# microzed_breakout_v0_6.net
KiCad netlist of a schematic drawn in EAGLE
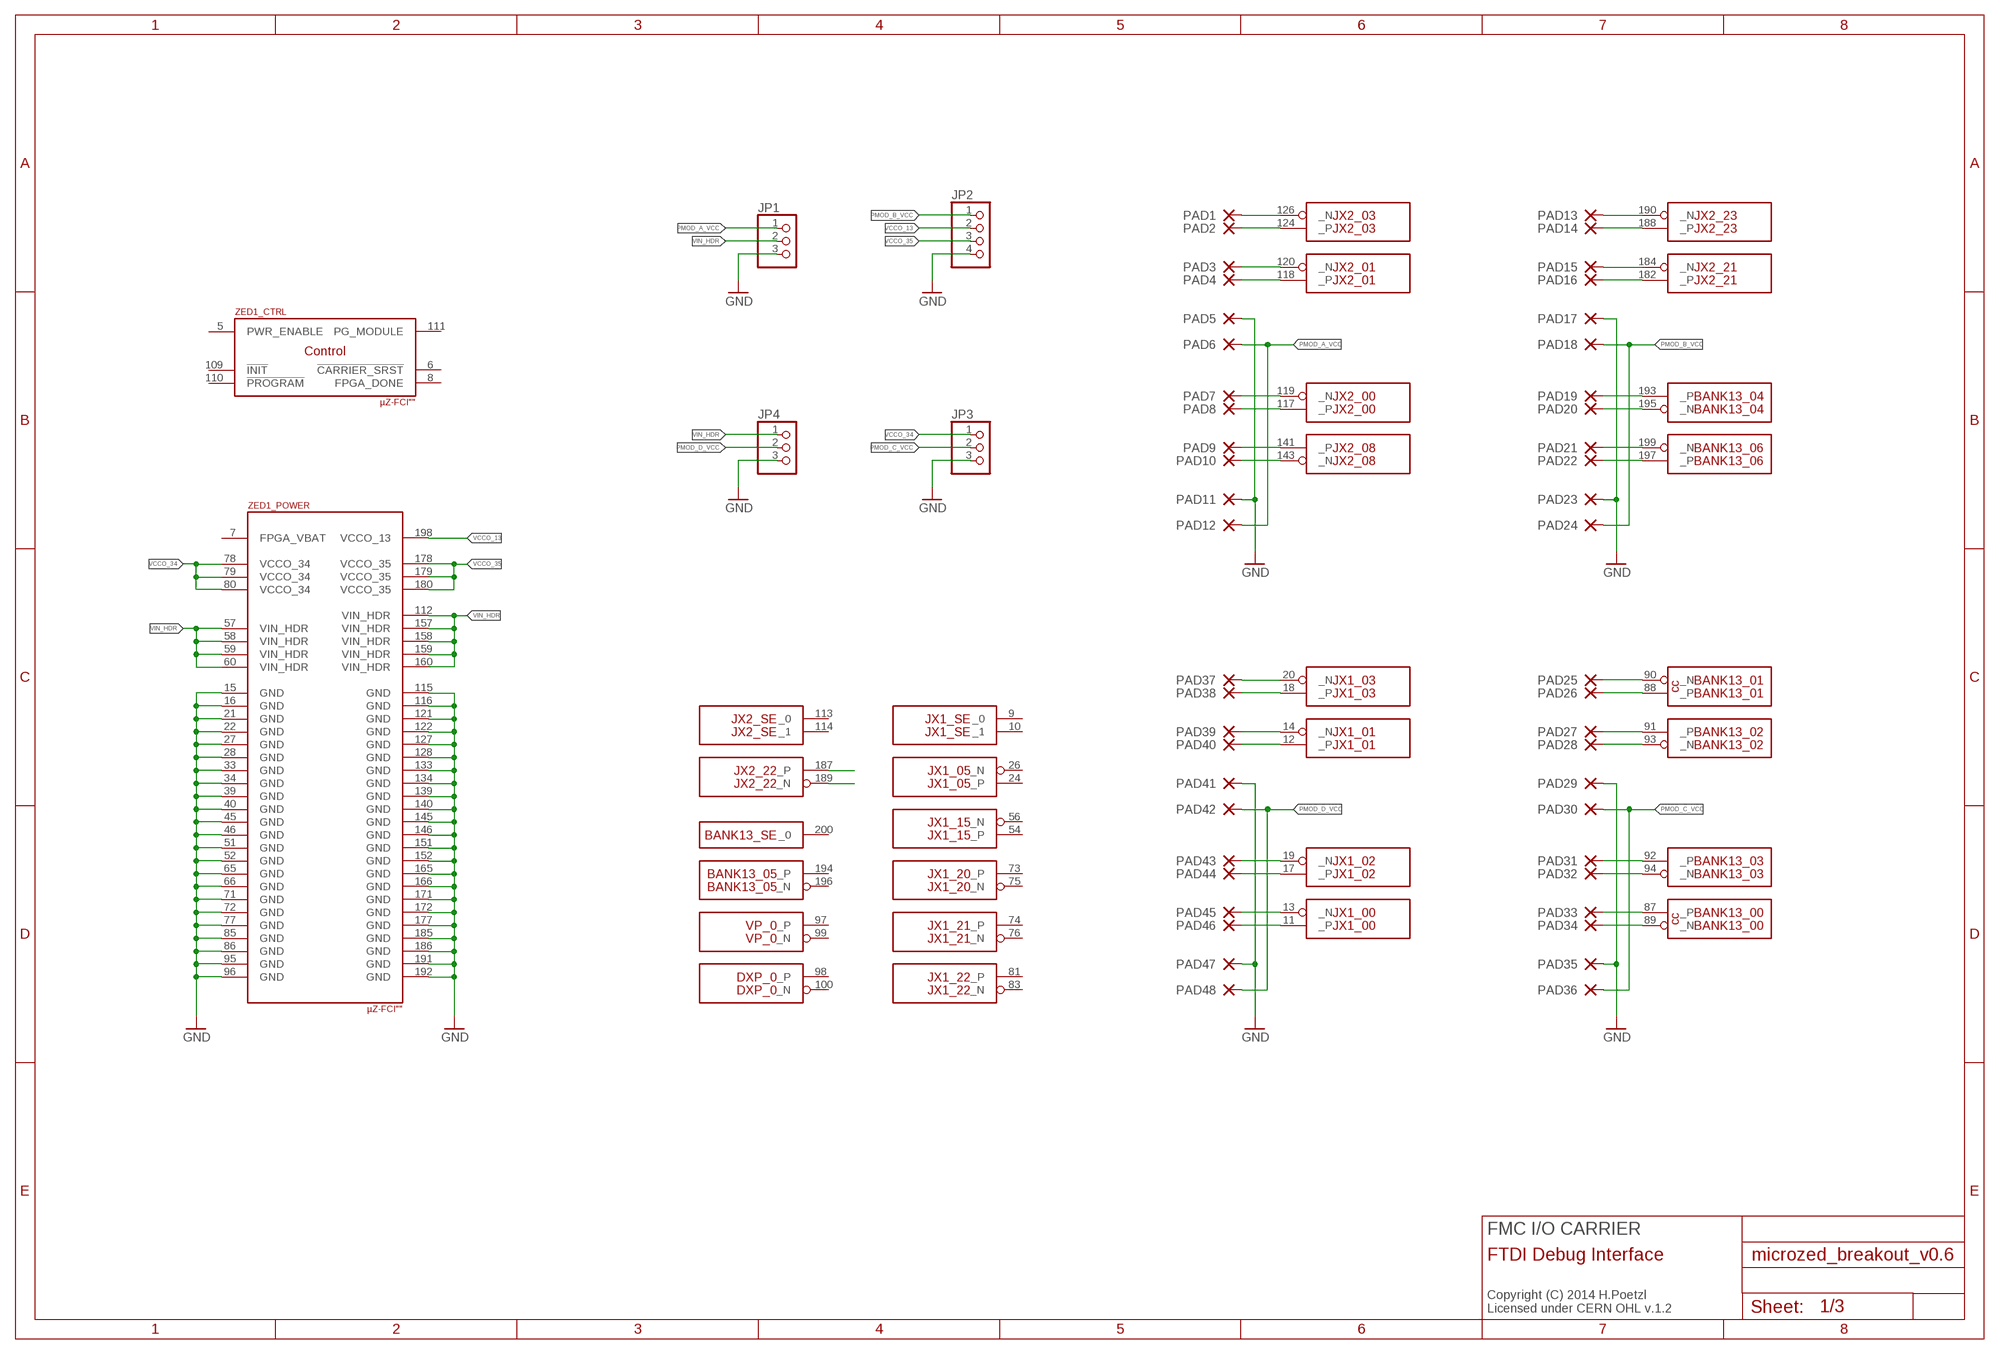
[diagram p0: schematic, sheet 1]
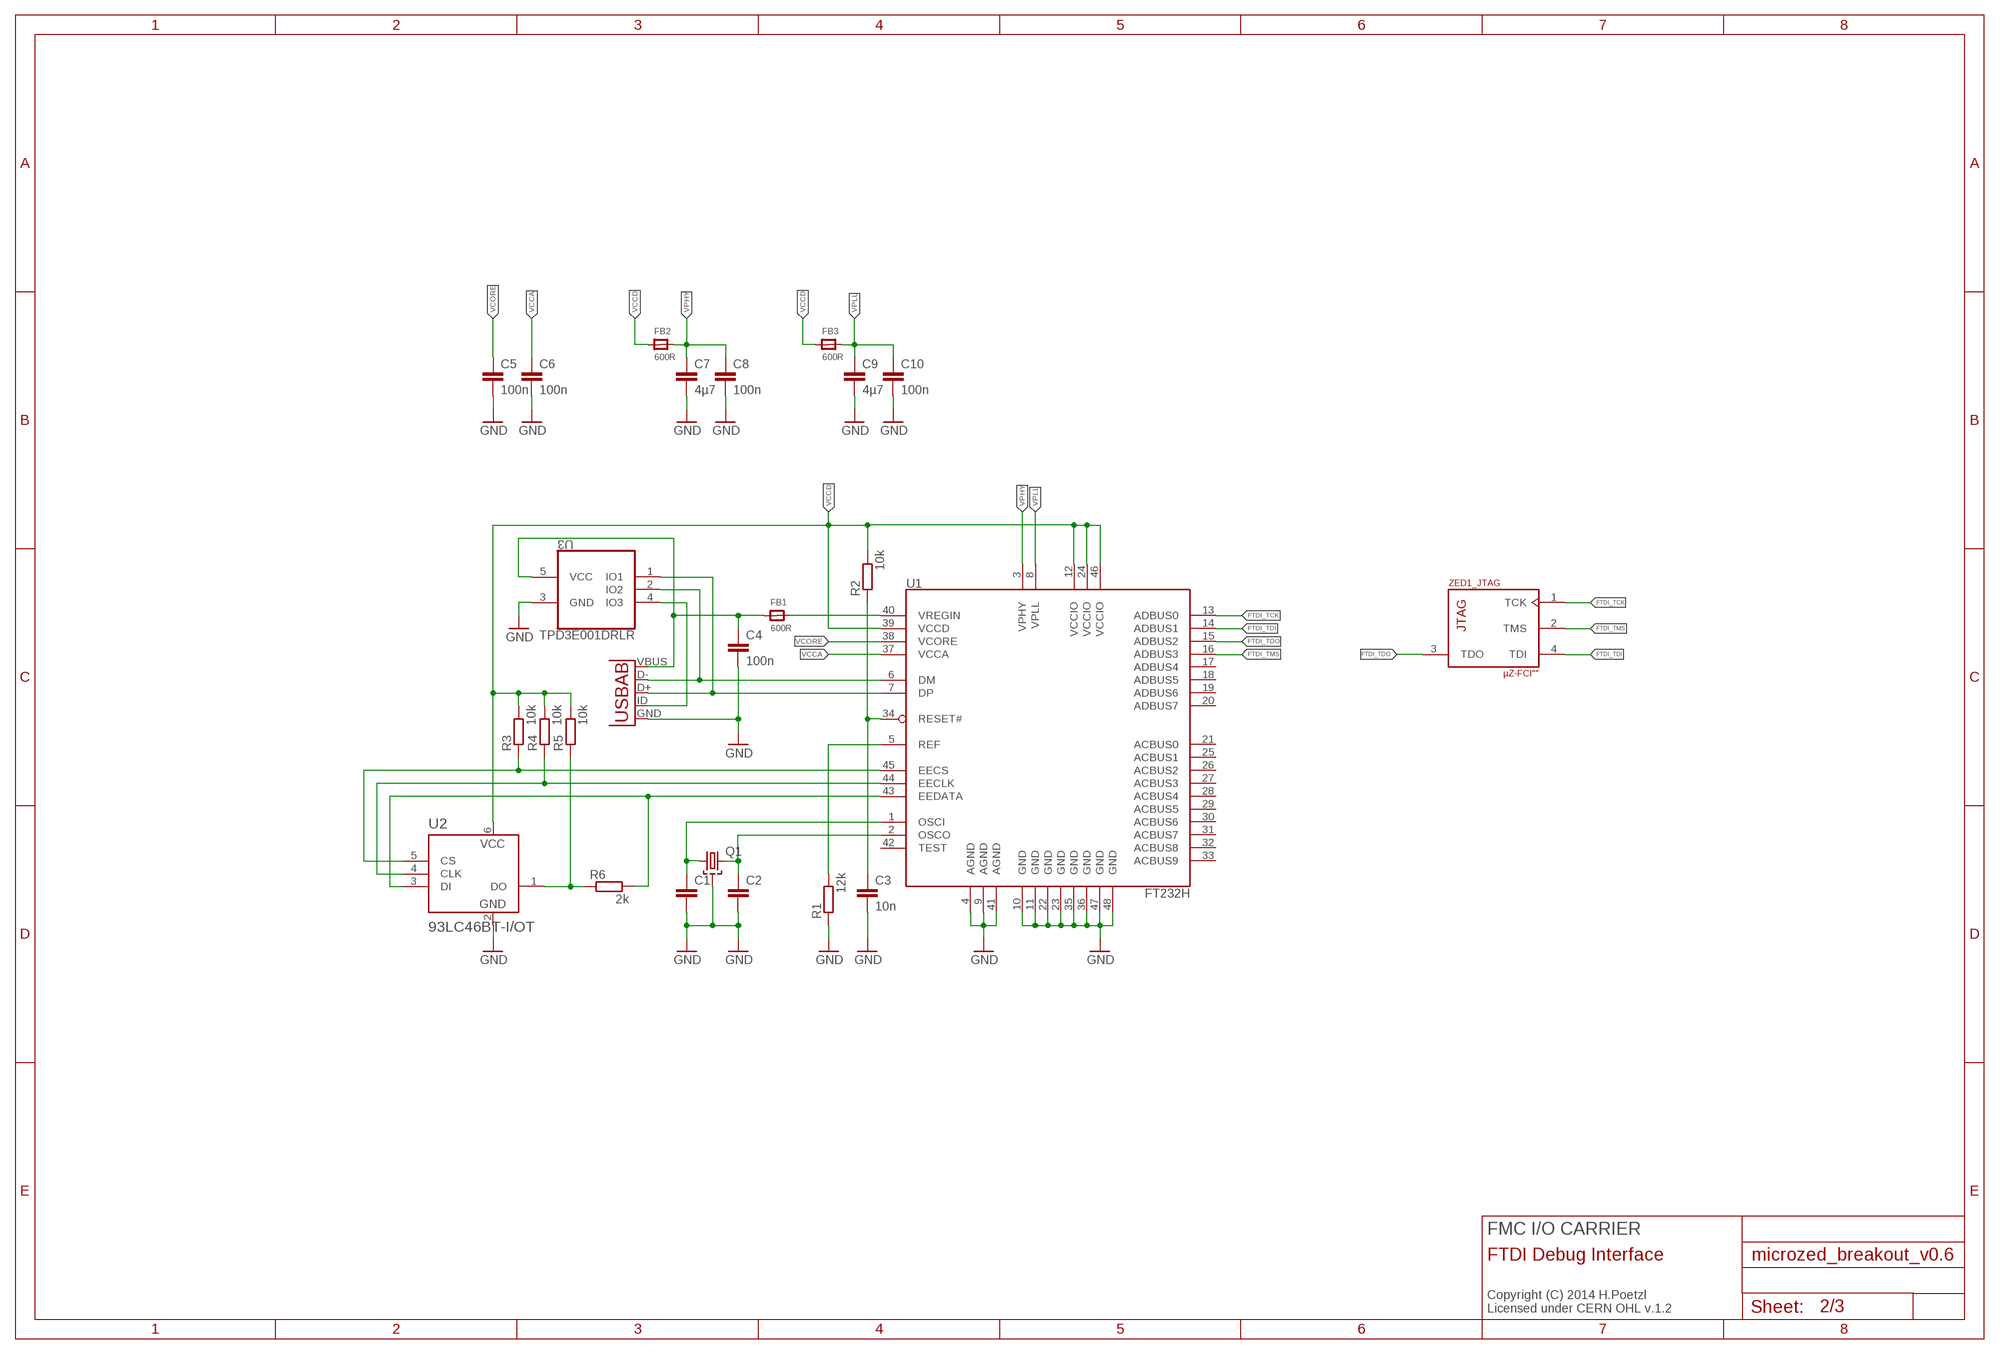
[diagram p1: schematic, sheet 2]
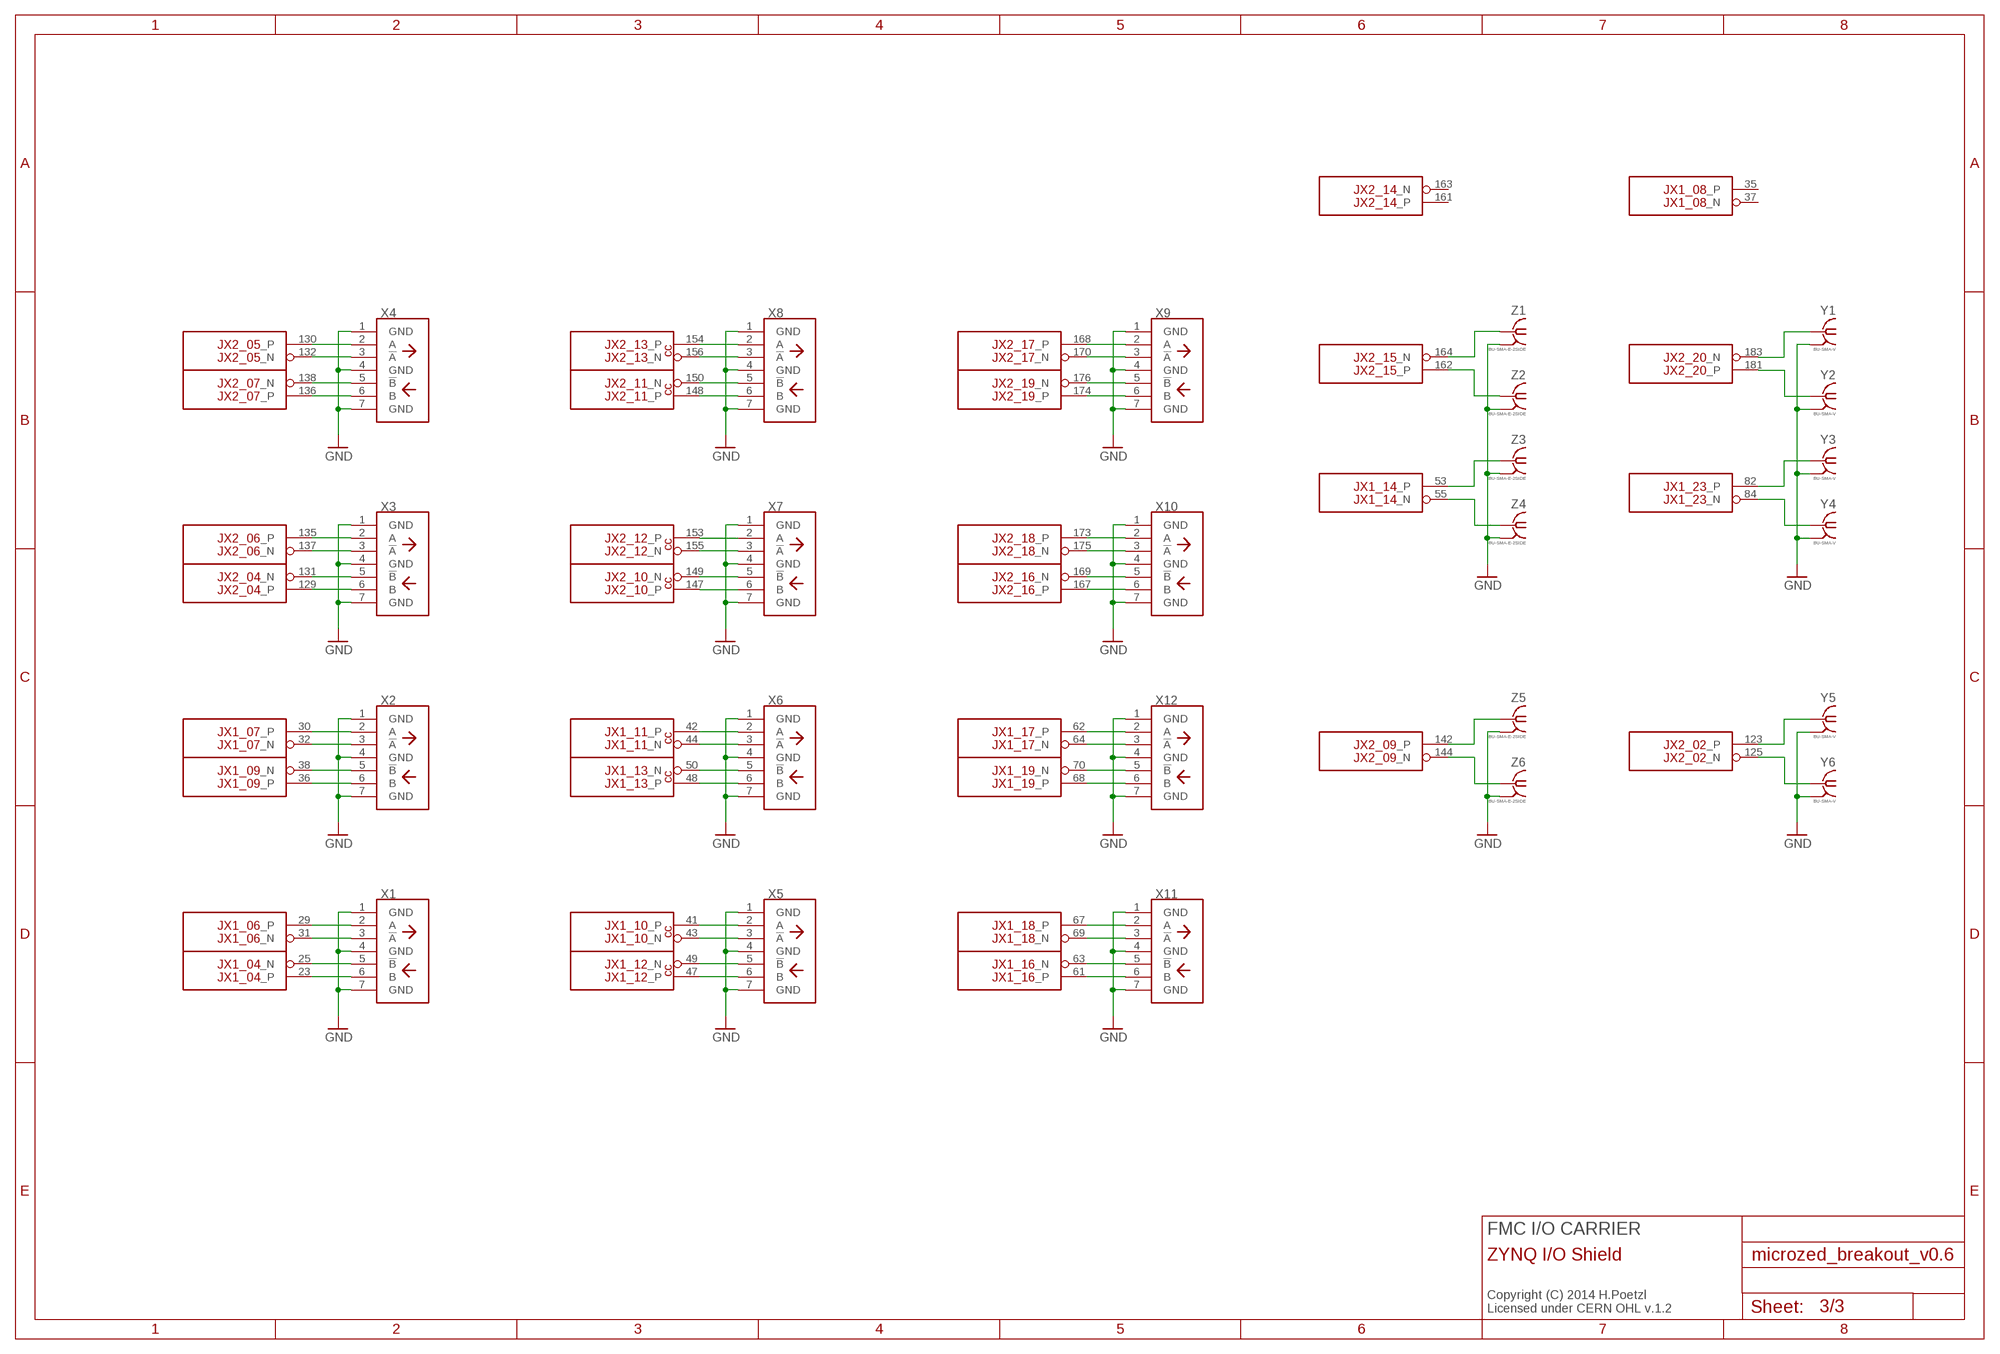
[diagram p2: schematic, sheet 3]

(export (version "E")
  (design (tool "Eeschema 10.0.6"))
  (components
    (comp (ref "JP1")
      (value "PINHD-1X03_2.54")
      (footprint "eagle-import:1X03")
      (libsource (lib "eagle-import") (part "PINHD-1X03_2.54"))
    )
    (comp (ref "JP2")
      (value "PINHD-1X04_2.54")
      (footprint "eagle-import:1X04")
      (libsource (lib "eagle-import") (part "PINHD-1X04_2.54"))
    )
    (comp (ref "JP3")
      (value "PINHD-1X03_2.54")
      (footprint "eagle-import:1X03")
      (libsource (lib "eagle-import") (part "PINHD-1X03_2.54"))
    )
    (comp (ref "JP4")
      (value "PINHD-1X03_2.54")
      (footprint "eagle-import:1X03")
      (libsource (lib "eagle-import") (part "PINHD-1X03_2.54"))
    )
    (comp (ref "PAD1")
      (value "SMD-PAD1.6X3.8MM-U")
      (footprint "eagle-import:1.6X3.8U-MM")
      (libsource (lib "eagle-import") (part "SMD-PAD1.6X3.8MM-U"))
    )
    (comp (ref "PAD2")
      (value "SMD-PAD1.6X3.8MM-U")
      (footprint "eagle-import:1.6X3.8U-MM")
      (libsource (lib "eagle-import") (part "SMD-PAD1.6X3.8MM-U"))
    )
    (comp (ref "PAD3")
      (value "SMD-PAD1.6X3.8MM-U")
      (footprint "eagle-import:1.6X3.8U-MM")
      (libsource (lib "eagle-import") (part "SMD-PAD1.6X3.8MM-U"))
    )
    (comp (ref "PAD4")
      (value "SMD-PAD1.6X3.8MM-U")
      (footprint "eagle-import:1.6X3.8U-MM")
      (libsource (lib "eagle-import") (part "SMD-PAD1.6X3.8MM-U"))
    )
    (comp (ref "PAD5")
      (value "SMD-PAD1.6X3.8MM-U")
      (footprint "eagle-import:1.6X3.8U-MM")
      (libsource (lib "eagle-import") (part "SMD-PAD1.6X3.8MM-U"))
    )
    (comp (ref "PAD6")
      (value "SMD-PAD1.6X3.8MM-U")
      (footprint "eagle-import:1.6X3.8U-MM")
      (libsource (lib "eagle-import") (part "SMD-PAD1.6X3.8MM-U"))
    )
    (comp (ref "PAD7")
      (value "SMD-PAD1.6X3.8MM-U")
      (footprint "eagle-import:1.6X3.8U-MM")
      (libsource (lib "eagle-import") (part "SMD-PAD1.6X3.8MM-U"))
    )
    (comp (ref "PAD8")
      (value "SMD-PAD1.6X3.8MM-U")
      (footprint "eagle-import:1.6X3.8U-MM")
      (libsource (lib "eagle-import") (part "SMD-PAD1.6X3.8MM-U"))
    )
    (comp (ref "PAD9")
      (value "SMD-PAD1.6X3.8MM-U")
      (footprint "eagle-import:1.6X3.8U-MM")
      (libsource (lib "eagle-import") (part "SMD-PAD1.6X3.8MM-U"))
    )
    (comp (ref "PAD10")
      (value "SMD-PAD1.6X3.8MM-U")
      (footprint "eagle-import:1.6X3.8U-MM")
      (libsource (lib "eagle-import") (part "SMD-PAD1.6X3.8MM-U"))
    )
    (comp (ref "PAD11")
      (value "SMD-PAD1.6X3.8MM-U")
      (footprint "eagle-import:1.6X3.8U-MM")
      (libsource (lib "eagle-import") (part "SMD-PAD1.6X3.8MM-U"))
    )
    (comp (ref "PAD12")
      (value "SMD-PAD1.6X3.8MM-U")
      (footprint "eagle-import:1.6X3.8U-MM")
      (libsource (lib "eagle-import") (part "SMD-PAD1.6X3.8MM-U"))
    )
    (comp (ref "PAD13")
      (value "SMD-PAD1.6X3.8MM-U")
      (footprint "eagle-import:1.6X3.8U-MM")
      (libsource (lib "eagle-import") (part "SMD-PAD1.6X3.8MM-U"))
    )
    (comp (ref "PAD14")
      (value "SMD-PAD1.6X3.8MM-U")
      (footprint "eagle-import:1.6X3.8U-MM")
      (libsource (lib "eagle-import") (part "SMD-PAD1.6X3.8MM-U"))
    )
    (comp (ref "PAD15")
      (value "SMD-PAD1.6X3.8MM-U")
      (footprint "eagle-import:1.6X3.8U-MM")
      (libsource (lib "eagle-import") (part "SMD-PAD1.6X3.8MM-U"))
    )
    (comp (ref "PAD16")
      (value "SMD-PAD1.6X3.8MM-U")
      (footprint "eagle-import:1.6X3.8U-MM")
      (libsource (lib "eagle-import") (part "SMD-PAD1.6X3.8MM-U"))
    )
    (comp (ref "PAD17")
      (value "SMD-PAD1.6X3.8MM-U")
      (footprint "eagle-import:1.6X3.8U-MM")
      (libsource (lib "eagle-import") (part "SMD-PAD1.6X3.8MM-U"))
    )
    (comp (ref "PAD18")
      (value "SMD-PAD1.6X3.8MM-U")
      (footprint "eagle-import:1.6X3.8U-MM")
      (libsource (lib "eagle-import") (part "SMD-PAD1.6X3.8MM-U"))
    )
    (comp (ref "PAD19")
      (value "SMD-PAD1.6X3.8MM-U")
      (footprint "eagle-import:1.6X3.8U-MM")
      (libsource (lib "eagle-import") (part "SMD-PAD1.6X3.8MM-U"))
    )
    (comp (ref "PAD20")
      (value "SMD-PAD1.6X3.8MM-U")
      (footprint "eagle-import:1.6X3.8U-MM")
      (libsource (lib "eagle-import") (part "SMD-PAD1.6X3.8MM-U"))
    )
    (comp (ref "PAD21")
      (value "SMD-PAD1.6X3.8MM-U")
      (footprint "eagle-import:1.6X3.8U-MM")
      (libsource (lib "eagle-import") (part "SMD-PAD1.6X3.8MM-U"))
    )
    (comp (ref "PAD22")
      (value "SMD-PAD1.6X3.8MM-U")
      (footprint "eagle-import:1.6X3.8U-MM")
      (libsource (lib "eagle-import") (part "SMD-PAD1.6X3.8MM-U"))
    )
    (comp (ref "PAD23")
      (value "SMD-PAD1.6X3.8MM-U")
      (footprint "eagle-import:1.6X3.8U-MM")
      (libsource (lib "eagle-import") (part "SMD-PAD1.6X3.8MM-U"))
    )
    (comp (ref "PAD24")
      (value "SMD-PAD1.6X3.8MM-U")
      (footprint "eagle-import:1.6X3.8U-MM")
      (libsource (lib "eagle-import") (part "SMD-PAD1.6X3.8MM-U"))
    )
    (comp (ref "PAD25")
      (value "SMD-PAD1.6X3.8MM-U")
      (footprint "eagle-import:1.6X3.8U-MM")
      (libsource (lib "eagle-import") (part "SMD-PAD1.6X3.8MM-U"))
    )
    (comp (ref "PAD26")
      (value "SMD-PAD1.6X3.8MM-U")
      (footprint "eagle-import:1.6X3.8U-MM")
      (libsource (lib "eagle-import") (part "SMD-PAD1.6X3.8MM-U"))
    )
    (comp (ref "PAD27")
      (value "SMD-PAD1.6X3.8MM-U")
      (footprint "eagle-import:1.6X3.8U-MM")
      (libsource (lib "eagle-import") (part "SMD-PAD1.6X3.8MM-U"))
    )
    (comp (ref "PAD28")
      (value "SMD-PAD1.6X3.8MM-U")
      (footprint "eagle-import:1.6X3.8U-MM")
      (libsource (lib "eagle-import") (part "SMD-PAD1.6X3.8MM-U"))
    )
    (comp (ref "PAD29")
      (value "SMD-PAD1.6X3.8MM-U")
      (footprint "eagle-import:1.6X3.8U-MM")
      (libsource (lib "eagle-import") (part "SMD-PAD1.6X3.8MM-U"))
    )
    (comp (ref "PAD30")
      (value "SMD-PAD1.6X3.8MM-U")
      (footprint "eagle-import:1.6X3.8U-MM")
      (libsource (lib "eagle-import") (part "SMD-PAD1.6X3.8MM-U"))
    )
    (comp (ref "PAD31")
      (value "SMD-PAD1.6X3.8MM-U")
      (footprint "eagle-import:1.6X3.8U-MM")
      (libsource (lib "eagle-import") (part "SMD-PAD1.6X3.8MM-U"))
    )
    (comp (ref "PAD32")
      (value "SMD-PAD1.6X3.8MM-U")
      (footprint "eagle-import:1.6X3.8U-MM")
      (libsource (lib "eagle-import") (part "SMD-PAD1.6X3.8MM-U"))
    )
    (comp (ref "PAD33")
      (value "SMD-PAD1.6X3.8MM-U")
      (footprint "eagle-import:1.6X3.8U-MM")
      (libsource (lib "eagle-import") (part "SMD-PAD1.6X3.8MM-U"))
    )
    (comp (ref "PAD34")
      (value "SMD-PAD1.6X3.8MM-U")
      (footprint "eagle-import:1.6X3.8U-MM")
      (libsource (lib "eagle-import") (part "SMD-PAD1.6X3.8MM-U"))
    )
    (comp (ref "PAD35")
      (value "SMD-PAD1.6X3.8MM-U")
      (footprint "eagle-import:1.6X3.8U-MM")
      (libsource (lib "eagle-import") (part "SMD-PAD1.6X3.8MM-U"))
    )
    (comp (ref "PAD36")
      (value "SMD-PAD1.6X3.8MM-U")
      (footprint "eagle-import:1.6X3.8U-MM")
      (libsource (lib "eagle-import") (part "SMD-PAD1.6X3.8MM-U"))
    )
    (comp (ref "PAD37")
      (value "SMD-PAD1.6X3.8MM-U")
      (footprint "eagle-import:1.6X3.8U-MM")
      (libsource (lib "eagle-import") (part "SMD-PAD1.6X3.8MM-U"))
    )
    (comp (ref "PAD38")
      (value "SMD-PAD1.6X3.8MM-U")
      (footprint "eagle-import:1.6X3.8U-MM")
      (libsource (lib "eagle-import") (part "SMD-PAD1.6X3.8MM-U"))
    )
    (comp (ref "PAD39")
      (value "SMD-PAD1.6X3.8MM-U")
      (footprint "eagle-import:1.6X3.8U-MM")
      (libsource (lib "eagle-import") (part "SMD-PAD1.6X3.8MM-U"))
    )
    (comp (ref "PAD40")
      (value "SMD-PAD1.6X3.8MM-U")
      (footprint "eagle-import:1.6X3.8U-MM")
      (libsource (lib "eagle-import") (part "SMD-PAD1.6X3.8MM-U"))
    )
    (comp (ref "PAD41")
      (value "SMD-PAD1.6X3.8MM-U")
      (footprint "eagle-import:1.6X3.8U-MM")
      (libsource (lib "eagle-import") (part "SMD-PAD1.6X3.8MM-U"))
    )
    (comp (ref "PAD42")
      (value "SMD-PAD1.6X3.8MM-U")
      (footprint "eagle-import:1.6X3.8U-MM")
      (libsource (lib "eagle-import") (part "SMD-PAD1.6X3.8MM-U"))
    )
    (comp (ref "PAD43")
      (value "SMD-PAD1.6X3.8MM-U")
      (footprint "eagle-import:1.6X3.8U-MM")
      (libsource (lib "eagle-import") (part "SMD-PAD1.6X3.8MM-U"))
    )
    (comp (ref "PAD44")
      (value "SMD-PAD1.6X3.8MM-U")
      (footprint "eagle-import:1.6X3.8U-MM")
      (libsource (lib "eagle-import") (part "SMD-PAD1.6X3.8MM-U"))
    )
    (comp (ref "PAD45")
      (value "SMD-PAD1.6X3.8MM-U")
      (footprint "eagle-import:1.6X3.8U-MM")
      (libsource (lib "eagle-import") (part "SMD-PAD1.6X3.8MM-U"))
    )
    (comp (ref "PAD46")
      (value "SMD-PAD1.6X3.8MM-U")
      (footprint "eagle-import:1.6X3.8U-MM")
      (libsource (lib "eagle-import") (part "SMD-PAD1.6X3.8MM-U"))
    )
    (comp (ref "PAD47")
      (value "SMD-PAD1.6X3.8MM-U")
      (footprint "eagle-import:1.6X3.8U-MM")
      (libsource (lib "eagle-import") (part "SMD-PAD1.6X3.8MM-U"))
    )
    (comp (ref "PAD48")
      (value "SMD-PAD1.6X3.8MM-U")
      (footprint "eagle-import:1.6X3.8U-MM")
      (libsource (lib "eagle-import") (part "SMD-PAD1.6X3.8MM-U"))
    )
    (comp (ref "ZED1")
      (value "µZ-FCI\"\"")
      (footprint "eagle-import:µZ")
      (libsource (lib "eagle-import") (part "µZ-FCI{dblquote}{dblquote}"))
    )
    (comp (ref "C1")
      (value "C-EUC0402K")
      (footprint "eagle-import:C0402K")
      (libsource (lib "eagle-import") (part "C-EUC0402K"))
    )
    (comp (ref "C2")
      (value "C-EUC0402K")
      (footprint "eagle-import:C0402K")
      (libsource (lib "eagle-import") (part "C-EUC0402K"))
    )
    (comp (ref "C3")
      (value "10n")
      (footprint "eagle-import:C0402K")
      (libsource (lib "eagle-import") (part "C-EUC0402K"))
    )
    (comp (ref "C4")
      (value "100n")
      (footprint "eagle-import:C0402K")
      (libsource (lib "eagle-import") (part "C-EUC0402K"))
    )
    (comp (ref "C5")
      (value "100n")
      (footprint "eagle-import:C0402K")
      (libsource (lib "eagle-import") (part "C-EUC0402K"))
    )
    (comp (ref "C6")
      (value "100n")
      (footprint "eagle-import:C0402K")
      (libsource (lib "eagle-import") (part "C-EUC0402K"))
    )
    (comp (ref "C7")
      (value "4µ7")
      (footprint "eagle-import:C0402K")
      (libsource (lib "eagle-import") (part "C-EUC0402K"))
    )
    (comp (ref "C8")
      (value "100n")
      (footprint "eagle-import:C0402K")
      (libsource (lib "eagle-import") (part "C-EUC0402K"))
    )
    (comp (ref "C9")
      (value "4µ7")
      (footprint "eagle-import:C0402K")
      (libsource (lib "eagle-import") (part "C-EUC0402K"))
    )
    (comp (ref "C10")
      (value "100n")
      (footprint "eagle-import:C0402K")
      (libsource (lib "eagle-import") (part "C-EUC0402K"))
    )
    (comp (ref "FB1")
      (value "600R")
      (footprint "eagle-import:_0603MP")
      (libsource (lib "eagle-import") (part "FERRITE_0603MP"))
    )
    (comp (ref "FB2")
      (value "600R")
      (footprint "eagle-import:_0603MP")
      (libsource (lib "eagle-import") (part "FERRITE_0603MP"))
    )
    (comp (ref "FB3")
      (value "600R")
      (footprint "eagle-import:_0603MP")
      (libsource (lib "eagle-import") (part "FERRITE_0603MP"))
    )
    (comp (ref "Q1")
      (value "SMD-4P-2G-3.2X2.5")
      (footprint "eagle-import:ABM8G")
      (libsource (lib "eagle-import") (part "SMD-4P-2G-3.2X2.5"))
    )
    (comp (ref "R1")
      (value "12k")
      (footprint "eagle-import:R0402")
      (libsource (lib "eagle-import") (part "R-EU_R0402"))
    )
    (comp (ref "R2")
      (value "10k")
      (footprint "eagle-import:R0402")
      (libsource (lib "eagle-import") (part "R-EU_R0402"))
    )
    (comp (ref "R3")
      (value "10k")
      (footprint "eagle-import:R0402")
      (libsource (lib "eagle-import") (part "R-EU_R0402"))
    )
    (comp (ref "R4")
      (value "10k")
      (footprint "eagle-import:R0402")
      (libsource (lib "eagle-import") (part "R-EU_R0402"))
    )
    (comp (ref "R5")
      (value "10k")
      (footprint "eagle-import:R0402")
      (libsource (lib "eagle-import") (part "R-EU_R0402"))
    )
    (comp (ref "R6")
      (value "2k")
      (footprint "eagle-import:R0402")
      (libsource (lib "eagle-import") (part "R-EU_R0402"))
    )
    (comp (ref "U1")
      (value "FT232H")
      (footprint "eagle-import:LQFP48")
      (libsource (lib "eagle-import") (part "FT232H"))
    )
    (comp (ref "U2")
      (value "93LC46BT-I/OT")
      (footprint "eagle-import:SOT95P280X145-6N")
      (libsource (lib "eagle-import") (part "93LC46BT-I/OT"))
    )
    (comp (ref "U3")
      (value "TPD3E001DRLR")
      (footprint "eagle-import:SOT50P160X60-5N")
      (libsource (lib "eagle-import") (part "TPD3E001DRLR"))
    )
    (comp (ref "USB")
      (value "USB-AB")
      (footprint "eagle-import:USB-AB-MICRO-SMD")
      (libsource (lib "eagle-import") (part "USB-AB"))
    )
    (comp (ref "X1")
      (value "SATA7-SMD-VERT")
      (footprint "eagle-import:SATA7-SMD-VERT")
      (libsource (lib "eagle-import") (part "SATA7-SMD-VERT"))
    )
    (comp (ref "X2")
      (value "SATA7-VERT")
      (footprint "eagle-import:SATA7-VERT")
      (libsource (lib "eagle-import") (part "SATA7-VERT"))
    )
    (comp (ref "X3")
      (value "SATA7-VERT")
      (footprint "eagle-import:SATA7-VERT")
      (libsource (lib "eagle-import") (part "SATA7-VERT"))
    )
    (comp (ref "X4")
      (value "SATA7-SMD-VERT")
      (footprint "eagle-import:SATA7-SMD-VERT")
      (libsource (lib "eagle-import") (part "SATA7-SMD-VERT"))
    )
    (comp (ref "X5")
      (value "SATA7-SMD-VERT")
      (footprint "eagle-import:SATA7-SMD-VERT")
      (libsource (lib "eagle-import") (part "SATA7-SMD-VERT"))
    )
    (comp (ref "X6")
      (value "SATA7-VERT")
      (footprint "eagle-import:SATA7-VERT")
      (libsource (lib "eagle-import") (part "SATA7-VERT"))
    )
    (comp (ref "X7")
      (value "SATA7-VERT")
      (footprint "eagle-import:SATA7-VERT")
      (libsource (lib "eagle-import") (part "SATA7-VERT"))
    )
    (comp (ref "X8")
      (value "SATA7-SMD-VERT")
      (footprint "eagle-import:SATA7-SMD-VERT")
      (libsource (lib "eagle-import") (part "SATA7-SMD-VERT"))
    )
    (comp (ref "X9")
      (value "SATA7-SMD-VERT")
      (footprint "eagle-import:SATA7-SMD-VERT")
      (libsource (lib "eagle-import") (part "SATA7-SMD-VERT"))
    )
    (comp (ref "X10")
      (value "SATA7-VERT")
      (footprint "eagle-import:SATA7-VERT")
      (libsource (lib "eagle-import") (part "SATA7-VERT"))
    )
    (comp (ref "X11")
      (value "SATA7-SMD-VERT")
      (footprint "eagle-import:SATA7-SMD-VERT")
      (libsource (lib "eagle-import") (part "SATA7-SMD-VERT"))
    )
    (comp (ref "X12")
      (value "SATA7-VERT")
      (footprint "eagle-import:SATA7-VERT")
      (libsource (lib "eagle-import") (part "SATA7-VERT"))
    )
    (comp (ref "Y1")
      (value "BU-SMA-V")
      (footprint "eagle-import:BU-SMA-V")
      (libsource (lib "eagle-import") (part "BU-SMA-V"))
    )
    (comp (ref "Y2")
      (value "BU-SMA-V")
      (footprint "eagle-import:BU-SMA-V")
      (libsource (lib "eagle-import") (part "BU-SMA-V"))
    )
    (comp (ref "Y3")
      (value "BU-SMA-V")
      (footprint "eagle-import:BU-SMA-V")
      (libsource (lib "eagle-import") (part "BU-SMA-V"))
    )
    (comp (ref "Y4")
      (value "BU-SMA-V")
      (footprint "eagle-import:BU-SMA-V")
      (libsource (lib "eagle-import") (part "BU-SMA-V"))
    )
    (comp (ref "Y5")
      (value "BU-SMA-V")
      (footprint "eagle-import:BU-SMA-V")
      (libsource (lib "eagle-import") (part "BU-SMA-V"))
    )
    (comp (ref "Y6")
      (value "BU-SMA-V")
      (footprint "eagle-import:BU-SMA-V")
      (libsource (lib "eagle-import") (part "BU-SMA-V"))
    )
    (comp (ref "Z1")
      (value "BU-SMA-E-2SIDE")
      (footprint "eagle-import:SMA_EDGE_2SIDE")
      (libsource (lib "eagle-import") (part "BU-SMA-E-2SIDE"))
    )
    (comp (ref "Z2")
      (value "BU-SMA-E-2SIDE")
      (footprint "eagle-import:SMA_EDGE_2SIDE")
      (libsource (lib "eagle-import") (part "BU-SMA-E-2SIDE"))
    )
    (comp (ref "Z3")
      (value "BU-SMA-E-2SIDE")
      (footprint "eagle-import:SMA_EDGE_2SIDE")
      (libsource (lib "eagle-import") (part "BU-SMA-E-2SIDE"))
    )
    (comp (ref "Z4")
      (value "BU-SMA-E-2SIDE")
      (footprint "eagle-import:SMA_EDGE_2SIDE")
      (libsource (lib "eagle-import") (part "BU-SMA-E-2SIDE"))
    )
    (comp (ref "Z5")
      (value "BU-SMA-E-2SIDE")
      (footprint "eagle-import:SMA_EDGE_2SIDE")
      (libsource (lib "eagle-import") (part "BU-SMA-E-2SIDE"))
    )
    (comp (ref "Z6")
      (value "BU-SMA-E-2SIDE")
      (footprint "eagle-import:SMA_EDGE_2SIDE")
      (libsource (lib "eagle-import") (part "BU-SMA-E-2SIDE"))
    )
  )
  (nets
    (net (code "1") (name "FPGA_VBAT") (class "Default")
      (node (ref "ZED1") (pin "7") (pinfunction "FPGA_VBAT_7") (pintype "power_in"))
    )
    (net (code "2") (name "FTDI_TCK") (class "Default")
      (node (ref "U1") (pin "13") (pinfunction "ADBUS0_13") (pintype "output"))
      (node (ref "ZED1") (pin "1") (pinfunction "TCK_1") (pintype "output"))
    )
    (net (code "3") (name "FTDI_TDI") (class "Default")
      (node (ref "U1") (pin "14") (pinfunction "ADBUS1_14") (pintype "input"))
      (node (ref "ZED1") (pin "4") (pinfunction "TDI_4") (pintype "output"))
    )
    (net (code "4") (name "FTDI_TDO") (class "Default")
      (node (ref "U1") (pin "15") (pinfunction "ADBUS2_15") (pintype "output"))
      (node (ref "ZED1") (pin "3") (pinfunction "TDO_3") (pintype "input"))
    )
    (net (code "5") (name "FTDI_TMS") (class "Default")
      (node (ref "U1") (pin "16") (pinfunction "ADBUS3_16") (pintype "input"))
      (node (ref "ZED1") (pin "2") (pinfunction "TMS_2") (pintype "output"))
    )
    (net (code "6") (name "GND") (class "Default")
      (node (ref "C1") (pin "2") (pinfunction "2_2") (pintype "passive"))
      (node (ref "C10") (pin "2") (pinfunction "2_2") (pintype "passive"))
      (node (ref "C2") (pin "2") (pinfunction "2_2") (pintype "passive"))
      (node (ref "C3") (pin "2") (pinfunction "2_2") (pintype "passive"))
      (node (ref "C4") (pin "2") (pinfunction "2_2") (pintype "passive"))
      (node (ref "C5") (pin "2") (pinfunction "2_2") (pintype "passive"))
      (node (ref "C6") (pin "2") (pinfunction "2_2") (pintype "passive"))
      (node (ref "C7") (pin "2") (pinfunction "2_2") (pintype "passive"))
      (node (ref "C8") (pin "2") (pinfunction "2_2") (pintype "passive"))
      (node (ref "C9") (pin "2") (pinfunction "2_2") (pintype "passive"))
      (node (ref "JP1") (pin "3") (pinfunction "3_3") (pintype "passive"))
      (node (ref "JP2") (pin "4") (pinfunction "4_4") (pintype "passive"))
      (node (ref "JP3") (pin "3") (pinfunction "3_3") (pintype "passive"))
      (node (ref "JP4") (pin "3") (pinfunction "3_3") (pintype "passive"))
      (node (ref "PAD11") (pin "1") (pinfunction "P_1") (pintype "passive"))
      (node (ref "PAD17") (pin "1") (pinfunction "P_1") (pintype "passive"))
      (node (ref "PAD23") (pin "1") (pinfunction "P_1") (pintype "passive"))
      (node (ref "PAD29") (pin "1") (pinfunction "P_1") (pintype "passive"))
      (node (ref "PAD35") (pin "1") (pinfunction "P_1") (pintype "passive"))
      (node (ref "PAD41") (pin "1") (pinfunction "P_1") (pintype "passive"))
      (node (ref "PAD47") (pin "1") (pinfunction "P_1") (pintype "passive"))
      (node (ref "PAD5") (pin "1") (pinfunction "P_1") (pintype "passive"))
      (node (ref "Q1") (pin "2") (pinfunction "GND_2") (pintype "power_in"))
      (node (ref "Q1") (pin "4") (pinfunction "GND_4") (pintype "power_in"))
      (node (ref "R1") (pin "1") (pinfunction "1_1") (pintype "passive"))
      (node (ref "U1") (pin "10") (pinfunction "GND_10") (pintype "power_in"))
      (node (ref "U1") (pin "11") (pinfunction "GND_11") (pintype "power_in"))
      (node (ref "U1") (pin "22") (pinfunction "GND_22") (pintype "power_in"))
      (node (ref "U1") (pin "23") (pinfunction "GND_23") (pintype "power_in"))
      (node (ref "U1") (pin "35") (pinfunction "GND_35") (pintype "power_in"))
      (node (ref "U1") (pin "36") (pinfunction "GND_36") (pintype "power_in"))
      (node (ref "U1") (pin "4") (pinfunction "AGND_4") (pintype "power_in"))
      (node (ref "U1") (pin "41") (pinfunction "AGND_41") (pintype "power_in"))
      (node (ref "U1") (pin "47") (pinfunction "GND_47") (pintype "power_in"))
      (node (ref "U1") (pin "48") (pinfunction "GND_48") (pintype "power_in"))
      (node (ref "U1") (pin "9") (pinfunction "AGND_9") (pintype "power_in"))
      (node (ref "U2") (pin "2") (pinfunction "VSS_2") (pintype "power_in"))
      (node (ref "U3") (pin "3") (pinfunction "GND_3") (pintype "passive"))
      (node (ref "USB") (pin "GND") (pinfunction "GND_GND") (pintype "bidirectional"))
      (node (ref "X1") (pin "1") (pinfunction "GND_1") (pintype "passive"))
      (node (ref "X1") (pin "4") (pinfunction "GND_4") (pintype "passive"))
      (node (ref "X1") (pin "7") (pinfunction "GND_7") (pintype "passive"))
      (node (ref "X10") (pin "1") (pinfunction "GND_1") (pintype "passive"))
      (node (ref "X10") (pin "4") (pinfunction "GND_4") (pintype "passive"))
      (node (ref "X10") (pin "7") (pinfunction "GND_7") (pintype "passive"))
      (node (ref "X11") (pin "1") (pinfunction "GND_1") (pintype "passive"))
      (node (ref "X11") (pin "4") (pinfunction "GND_4") (pintype "passive"))
      (node (ref "X11") (pin "7") (pinfunction "GND_7") (pintype "passive"))
      (node (ref "X12") (pin "1") (pinfunction "GND_1") (pintype "passive"))
      (node (ref "X12") (pin "4") (pinfunction "GND_4") (pintype "passive"))
      (node (ref "X12") (pin "7") (pinfunction "GND_7") (pintype "passive"))
      (node (ref "X2") (pin "1") (pinfunction "GND_1") (pintype "passive"))
      (node (ref "X2") (pin "4") (pinfunction "GND_4") (pintype "passive"))
      (node (ref "X2") (pin "7") (pinfunction "GND_7") (pintype "passive"))
      (node (ref "X3") (pin "1") (pinfunction "GND_1") (pintype "passive"))
      (node (ref "X3") (pin "4") (pinfunction "GND_4") (pintype "passive"))
      (node (ref "X3") (pin "7") (pinfunction "GND_7") (pintype "passive"))
      (node (ref "X4") (pin "1") (pinfunction "GND_1") (pintype "passive"))
      (node (ref "X4") (pin "4") (pinfunction "GND_4") (pintype "passive"))
      (node (ref "X4") (pin "7") (pinfunction "GND_7") (pintype "passive"))
      (node (ref "X5") (pin "1") (pinfunction "GND_1") (pintype "passive"))
      (node (ref "X5") (pin "4") (pinfunction "GND_4") (pintype "passive"))
      (node (ref "X5") (pin "7") (pinfunction "GND_7") (pintype "passive"))
      (node (ref "X6") (pin "1") (pinfunction "GND_1") (pintype "passive"))
      (node (ref "X6") (pin "4") (pinfunction "GND_4") (pintype "passive"))
      (node (ref "X6") (pin "7") (pinfunction "GND_7") (pintype "passive"))
      (node (ref "X7") (pin "1") (pinfunction "GND_1") (pintype "passive"))
      (node (ref "X7") (pin "4") (pinfunction "GND_4") (pintype "passive"))
      (node (ref "X7") (pin "7") (pinfunction "GND_7") (pintype "passive"))
      (node (ref "X8") (pin "1") (pinfunction "GND_1") (pintype "passive"))
      (node (ref "X8") (pin "4") (pinfunction "GND_4") (pintype "passive"))
      (node (ref "X8") (pin "7") (pinfunction "GND_7") (pintype "passive"))
      (node (ref "X9") (pin "1") (pinfunction "GND_1") (pintype "passive"))
      (node (ref "X9") (pin "4") (pinfunction "GND_4") (pintype "passive"))
      (node (ref "X9") (pin "7") (pinfunction "GND_7") (pintype "passive"))
      (node (ref "Y1") (pin "2") (pinfunction "2_2") (pintype "passive"))
      (node (ref "Y1") (pin "3") (pinfunction "2_3") (pintype "passive"))
      (node (ref "Y1") (pin "4") (pinfunction "2_4") (pintype "passive"))
      (node (ref "Y1") (pin "5") (pinfunction "2_5") (pintype "passive"))
      (node (ref "Y2") (pin "2") (pinfunction "2_2") (pintype "passive"))
      (node (ref "Y2") (pin "3") (pinfunction "2_3") (pintype "passive"))
      (node (ref "Y2") (pin "4") (pinfunction "2_4") (pintype "passive"))
      (node (ref "Y2") (pin "5") (pinfunction "2_5") (pintype "passive"))
      (node (ref "Y3") (pin "2") (pinfunction "2_2") (pintype "passive"))
      (node (ref "Y3") (pin "3") (pinfunction "2_3") (pintype "passive"))
      (node (ref "Y3") (pin "4") (pinfunction "2_4") (pintype "passive"))
      (node (ref "Y3") (pin "5") (pinfunction "2_5") (pintype "passive"))
      (node (ref "Y4") (pin "2") (pinfunction "2_2") (pintype "passive"))
      (node (ref "Y4") (pin "3") (pinfunction "2_3") (pintype "passive"))
      (node (ref "Y4") (pin "4") (pinfunction "2_4") (pintype "passive"))
      (node (ref "Y4") (pin "5") (pinfunction "2_5") (pintype "passive"))
      (node (ref "Y5") (pin "2") (pinfunction "2_2") (pintype "passive"))
      (node (ref "Y5") (pin "3") (pinfunction "2_3") (pintype "passive"))
      (node (ref "Y5") (pin "4") (pinfunction "2_4") (pintype "passive"))
      (node (ref "Y5") (pin "5") (pinfunction "2_5") (pintype "passive"))
      (node (ref "Y6") (pin "2") (pinfunction "2_2") (pintype "passive"))
      (node (ref "Y6") (pin "3") (pinfunction "2_3") (pintype "passive"))
      (node (ref "Y6") (pin "4") (pinfunction "2_4") (pintype "passive"))
      (node (ref "Y6") (pin "5") (pinfunction "2_5") (pintype "passive"))
      (node (ref "Z1") (pin "2@1") (pinfunction "2_2@1") (pintype "passive"))
      (node (ref "Z1") (pin "2@2") (pinfunction "2_2@2") (pintype "passive"))
      (node (ref "Z1") (pin "2@3") (pinfunction "2_2@3") (pintype "passive"))
      (node (ref "Z1") (pin "2@4") (pinfunction "2_2@4") (pintype "passive"))
      (node (ref "Z2") (pin "2@1") (pinfunction "2_2@1") (pintype "passive"))
      (node (ref "Z2") (pin "2@2") (pinfunction "2_2@2") (pintype "passive"))
      (node (ref "Z2") (pin "2@3") (pinfunction "2_2@3") (pintype "passive"))
      (node (ref "Z2") (pin "2@4") (pinfunction "2_2@4") (pintype "passive"))
      (node (ref "Z3") (pin "2@1") (pinfunction "2_2@1") (pintype "passive"))
      (node (ref "Z3") (pin "2@2") (pinfunction "2_2@2") (pintype "passive"))
      (node (ref "Z3") (pin "2@3") (pinfunction "2_2@3") (pintype "passive"))
      (node (ref "Z3") (pin "2@4") (pinfunction "2_2@4") (pintype "passive"))
      (node (ref "Z4") (pin "2@1") (pinfunction "2_2@1") (pintype "passive"))
      (node (ref "Z4") (pin "2@2") (pinfunction "2_2@2") (pintype "passive"))
      (node (ref "Z4") (pin "2@3") (pinfunction "2_2@3") (pintype "passive"))
      (node (ref "Z4") (pin "2@4") (pinfunction "2_2@4") (pintype "passive"))
      (node (ref "Z5") (pin "2@1") (pinfunction "2_2@1") (pintype "passive"))
      (node (ref "Z5") (pin "2@2") (pinfunction "2_2@2") (pintype "passive"))
      (node (ref "Z5") (pin "2@3") (pinfunction "2_2@3") (pintype "passive"))
      (node (ref "Z5") (pin "2@4") (pinfunction "2_2@4") (pintype "passive"))
      (node (ref "Z6") (pin "2@1") (pinfunction "2_2@1") (pintype "passive"))
      (node (ref "Z6") (pin "2@2") (pinfunction "2_2@2") (pintype "passive"))
      (node (ref "Z6") (pin "2@3") (pinfunction "2_2@3") (pintype "passive"))
      (node (ref "Z6") (pin "2@4") (pinfunction "2_2@4") (pintype "passive"))
      (node (ref "ZED1") (pin "115") (pinfunction "GND_115") (pintype "power_in"))
      (node (ref "ZED1") (pin "116") (pinfunction "GND_116") (pintype "power_in"))
      (node (ref "ZED1") (pin "121") (pinfunction "GND_121") (pintype "power_in"))
      (node (ref "ZED1") (pin "122") (pinfunction "GND_122") (pintype "power_in"))
      (node (ref "ZED1") (pin "127") (pinfunction "GND_127") (pintype "power_in"))
      (node (ref "ZED1") (pin "128") (pinfunction "GND_128") (pintype "power_in"))
      (node (ref "ZED1") (pin "133") (pinfunction "GND_133") (pintype "power_in"))
      (node (ref "ZED1") (pin "134") (pinfunction "GND_134") (pintype "power_in"))
      (node (ref "ZED1") (pin "139") (pinfunction "GND_139") (pintype "power_in"))
      (node (ref "ZED1") (pin "140") (pinfunction "GND_140") (pintype "power_in"))
      (node (ref "ZED1") (pin "145") (pinfunction "GND_145") (pintype "power_in"))
      (node (ref "ZED1") (pin "146") (pinfunction "GND_146") (pintype "power_in"))
      (node (ref "ZED1") (pin "15") (pinfunction "GND_15") (pintype "power_in"))
      (node (ref "ZED1") (pin "151") (pinfunction "GND_151") (pintype "power_in"))
      (node (ref "ZED1") (pin "152") (pinfunction "GND_152") (pintype "power_in"))
      (node (ref "ZED1") (pin "16") (pinfunction "GND_16") (pintype "power_in"))
      (node (ref "ZED1") (pin "165") (pinfunction "GND_165") (pintype "power_in"))
      (node (ref "ZED1") (pin "166") (pinfunction "GND_166") (pintype "power_in"))
      (node (ref "ZED1") (pin "171") (pinfunction "GND_171") (pintype "power_in"))
      (node (ref "ZED1") (pin "172") (pinfunction "GND_172") (pintype "power_in"))
      (node (ref "ZED1") (pin "177") (pinfunction "GND_177") (pintype "power_in"))
      (node (ref "ZED1") (pin "185") (pinfunction "GND_185") (pintype "power_in"))
      (node (ref "ZED1") (pin "186") (pinfunction "GND_186") (pintype "power_in"))
      (node (ref "ZED1") (pin "191") (pinfunction "GND_191") (pintype "power_in"))
      (node (ref "ZED1") (pin "192") (pinfunction "GND_192") (pintype "power_in"))
      (node (ref "ZED1") (pin "21") (pinfunction "GND_21") (pintype "power_in"))
      (node (ref "ZED1") (pin "22") (pinfunction "GND_22") (pintype "power_in"))
      (node (ref "ZED1") (pin "27") (pinfunction "GND_27") (pintype "power_in"))
      (node (ref "ZED1") (pin "28") (pinfunction "GND_28") (pintype "power_in"))
      (node (ref "ZED1") (pin "33") (pinfunction "GND_33") (pintype "power_in"))
      (node (ref "ZED1") (pin "34") (pinfunction "GND_34") (pintype "power_in"))
      (node (ref "ZED1") (pin "39") (pinfunction "GND_39") (pintype "power_in"))
      (node (ref "ZED1") (pin "40") (pinfunction "GND_40") (pintype "power_in"))
      (node (ref "ZED1") (pin "45") (pinfunction "GND_45") (pintype "power_in"))
      (node (ref "ZED1") (pin "46") (pinfunction "GND_46") (pintype "power_in"))
      (node (ref "ZED1") (pin "51") (pinfunction "GND_51") (pintype "power_in"))
      (node (ref "ZED1") (pin "52") (pinfunction "GND_52") (pintype "power_in"))
      (node (ref "ZED1") (pin "65") (pinfunction "GND_65") (pintype "power_in"))
      (node (ref "ZED1") (pin "66") (pinfunction "GND_66") (pintype "power_in"))
      (node (ref "ZED1") (pin "71") (pinfunction "GND_71") (pintype "power_in"))
      (node (ref "ZED1") (pin "72") (pinfunction "GND_72") (pintype "power_in"))
      (node (ref "ZED1") (pin "77") (pinfunction "GND_77") (pintype "power_in"))
      (node (ref "ZED1") (pin "85") (pinfunction "GND_85") (pintype "power_in"))
      (node (ref "ZED1") (pin "86") (pinfunction "GND_86") (pintype "power_in"))
      (node (ref "ZED1") (pin "95") (pinfunction "GND_95") (pintype "power_in"))
      (node (ref "ZED1") (pin "96") (pinfunction "GND_96") (pintype "power_in"))
    )
    (net (code "7") (name "Net-(FB1-P$1)") (class "Default")
      (node (ref "C4") (pin "1") (pinfunction "1_1") (pintype "passive"))
      (node (ref "FB1") (pin "1") (pinfunction "P$1_1") (pintype "passive"))
      (node (ref "U3") (pin "5") (pinfunction "VCC_5") (pintype "power_in"))
      (node (ref "USB") (pin "VBUS") (pinfunction "VBUS_VBUS") (pintype "bidirectional"))
    )
    (net (code "8") (name "Net-(FB1-P$2)") (class "Default")
      (node (ref "FB1") (pin "2") (pinfunction "P$2_2") (pintype "passive"))
      (node (ref "U1") (pin "40") (pinfunction "VREGIN_40") (pintype "power_in"))
    )
    (net (code "9") (name "Net-(PAD1-P)") (class "Default")
      (node (ref "PAD1") (pin "1") (pinfunction "P_1") (pintype "passive"))
      (node (ref "ZED1") (pin "126") (pinfunction "_N_126") (pintype "bidirectional"))
    )
    (net (code "10") (name "Net-(PAD2-P)") (class "Default")
      (node (ref "PAD2") (pin "1") (pinfunction "P_1") (pintype "passive"))
      (node (ref "ZED1") (pin "124") (pinfunction "_P_124") (pintype "bidirectional"))
    )
    (net (code "11") (name "Net-(PAD3-P)") (class "Default")
      (node (ref "PAD3") (pin "1") (pinfunction "P_1") (pintype "passive"))
      (node (ref "ZED1") (pin "120") (pinfunction "_N_120") (pintype "bidirectional"))
    )
    (net (code "12") (name "Net-(PAD4-P)") (class "Default")
      (node (ref "PAD4") (pin "1") (pinfunction "P_1") (pintype "passive"))
      (node (ref "ZED1") (pin "118") (pinfunction "_P_118") (pintype "bidirectional"))
    )
    (net (code "13") (name "Net-(PAD7-P)") (class "Default")
      (node (ref "PAD7") (pin "1") (pinfunction "P_1") (pintype "passive"))
      (node (ref "ZED1") (pin "119") (pinfunction "_N_119") (pintype "bidirectional"))
    )
    (net (code "14") (name "Net-(PAD8-P)") (class "Default")
      (node (ref "PAD8") (pin "1") (pinfunction "P_1") (pintype "passive"))
      (node (ref "ZED1") (pin "117") (pinfunction "_P_117") (pintype "bidirectional"))
    )
    (net (code "15") (name "Net-(PAD9-P)") (class "Default")
      (node (ref "PAD9") (pin "1") (pinfunction "P_1") (pintype "passive"))
      (node (ref "ZED1") (pin "141") (pinfunction "_P_141") (pintype "bidirectional"))
    )
    (net (code "16") (name "Net-(PAD10-P)") (class "Default")
      (node (ref "PAD10") (pin "1") (pinfunction "P_1") (pintype "passive"))
      (node (ref "ZED1") (pin "143") (pinfunction "_N_143") (pintype "bidirectional"))
    )
    (net (code "17") (name "Net-(PAD13-P)") (class "Default")
      (node (ref "PAD13") (pin "1") (pinfunction "P_1") (pintype "passive"))
      (node (ref "ZED1") (pin "190") (pinfunction "_N_190") (pintype "bidirectional"))
    )
    (net (code "18") (name "Net-(PAD14-P)") (class "Default")
      (node (ref "PAD14") (pin "1") (pinfunction "P_1") (pintype "passive"))
      (node (ref "ZED1") (pin "188") (pinfunction "_P_188") (pintype "bidirectional"))
    )
    (net (code "19") (name "Net-(PAD15-P)") (class "Default")
      (node (ref "PAD15") (pin "1") (pinfunction "P_1") (pintype "passive"))
      (node (ref "ZED1") (pin "184") (pinfunction "_N_184") (pintype "bidirectional"))
    )
    (net (code "20") (name "Net-(PAD16-P)") (class "Default")
      (node (ref "PAD16") (pin "1") (pinfunction "P_1") (pintype "passive"))
      (node (ref "ZED1") (pin "182") (pinfunction "_P_182") (pintype "bidirectional"))
    )
    (net (code "21") (name "Net-(PAD19-P)") (class "Default")
      (node (ref "PAD19") (pin "1") (pinfunction "P_1") (pintype "passive"))
      (node (ref "ZED1") (pin "193") (pinfunction "_P_193") (pintype "bidirectional"))
    )
    (net (code "22") (name "Net-(PAD20-P)") (class "Default")
      (node (ref "PAD20") (pin "1") (pinfunction "P_1") (pintype "passive"))
      (node (ref "ZED1") (pin "195") (pinfunction "_N_195") (pintype "bidirectional"))
    )
    (net (code "23") (name "Net-(PAD21-P)") (class "Default")
      (node (ref "PAD21") (pin "1") (pinfunction "P_1") (pintype "passive"))
      (node (ref "ZED1") (pin "199") (pinfunction "_N_199") (pintype "bidirectional"))
    )
    (net (code "24") (name "Net-(PAD22-P)") (class "Default")
      (node (ref "PAD22") (pin "1") (pinfunction "P_1") (pintype "passive"))
      (node (ref "ZED1") (pin "197") (pinfunction "_P_197") (pintype "bidirectional"))
    )
    (net (code "25") (name "Net-(PAD25-P)") (class "Default")
      (node (ref "PAD25") (pin "1") (pinfunction "P_1") (pintype "passive"))
      (node (ref "ZED1") (pin "90") (pinfunction "_N_90") (pintype "bidirectional"))
    )
    (net (code "26") (name "Net-(PAD26-P)") (class "Default")
      (node (ref "PAD26") (pin "1") (pinfunction "P_1") (pintype "passive"))
      (node (ref "ZED1") (pin "88") (pinfunction "_P_88") (pintype "bidirectional"))
    )
    (net (code "27") (name "Net-(PAD27-P)") (class "Default")
      (node (ref "PAD27") (pin "1") (pinfunction "P_1") (pintype "passive"))
      (node (ref "ZED1") (pin "91") (pinfunction "_P_91") (pintype "bidirectional"))
    )
    (net (code "28") (name "Net-(PAD28-P)") (class "Default")
      (node (ref "PAD28") (pin "1") (pinfunction "P_1") (pintype "passive"))
      (node (ref "ZED1") (pin "93") (pinfunction "_N_93") (pintype "bidirectional"))
    )
    (net (code "29") (name "Net-(PAD31-P)") (class "Default")
      (node (ref "PAD31") (pin "1") (pinfunction "P_1") (pintype "passive"))
      (node (ref "ZED1") (pin "92") (pinfunction "_P_92") (pintype "bidirectional"))
    )
    (net (code "30") (name "Net-(PAD32-P)") (class "Default")
      (node (ref "PAD32") (pin "1") (pinfunction "P_1") (pintype "passive"))
      (node (ref "ZED1") (pin "94") (pinfunction "_N_94") (pintype "bidirectional"))
    )
    (net (code "31") (name "Net-(PAD33-P)") (class "Default")
      (node (ref "PAD33") (pin "1") (pinfunction "P_1") (pintype "passive"))
      (node (ref "ZED1") (pin "87") (pinfunction "_P_87") (pintype "bidirectional"))
    )
    (net (code "32") (name "Net-(PAD34-P)") (class "Default")
      (node (ref "PAD34") (pin "1") (pinfunction "P_1") (pintype "passive"))
      (node (ref "ZED1") (pin "89") (pinfunction "_N_89") (pintype "bidirectional"))
    )
    (net (code "33") (name "Net-(PAD37-P)") (class "Default")
      (node (ref "PAD37") (pin "1") (pinfunction "P_1") (pintype "passive"))
      (node (ref "ZED1") (pin "20") (pinfunction "_N_20") (pintype "bidirectional"))
    )
    (net (code "34") (name "Net-(PAD38-P)") (class "Default")
      (node (ref "PAD38") (pin "1") (pinfunction "P_1") (pintype "passive"))
      (node (ref "ZED1") (pin "18") (pinfunction "_P_18") (pintype "bidirectional"))
    )
    (net (code "35") (name "Net-(PAD39-P)") (class "Default")
      (node (ref "PAD39") (pin "1") (pinfunction "P_1") (pintype "passive"))
      (node (ref "ZED1") (pin "14") (pinfunction "_N_14") (pintype "bidirectional"))
    )
    (net (code "36") (name "Net-(PAD40-P)") (class "Default")
      (node (ref "PAD40") (pin "1") (pinfunction "P_1") (pintype "passive"))
      (node (ref "ZED1") (pin "12") (pinfunction "_P_12") (pintype "bidirectional"))
    )
    (net (code "37") (name "Net-(PAD43-P)") (class "Default")
      (node (ref "PAD43") (pin "1") (pinfunction "P_1") (pintype "passive"))
      (node (ref "ZED1") (pin "19") (pinfunction "_N_19") (pintype "bidirectional"))
    )
    (net (code "38") (name "Net-(PAD44-P)") (class "Default")
      (node (ref "PAD44") (pin "1") (pinfunction "P_1") (pintype "passive"))
      (node (ref "ZED1") (pin "17") (pinfunction "_P_17") (pintype "bidirectional"))
    )
    (net (code "39") (name "Net-(PAD45-P)") (class "Default")
      (node (ref "PAD45") (pin "1") (pinfunction "P_1") (pintype "passive"))
      (node (ref "ZED1") (pin "13") (pinfunction "_N_13") (pintype "bidirectional"))
    )
    (net (code "40") (name "Net-(PAD46-P)") (class "Default")
      (node (ref "PAD46") (pin "1") (pinfunction "P_1") (pintype "passive"))
      (node (ref "ZED1") (pin "11") (pinfunction "_P_11") (pintype "bidirectional"))
    )
    (net (code "41") (name "Net-(Q1-2)") (class "Default")
      (node (ref "C2") (pin "1") (pinfunction "1_1") (pintype "passive"))
      (node (ref "Q1") (pin "3") (pinfunction "2_3") (pintype "passive"))
      (node (ref "U1") (pin "2") (pinfunction "OSCO_2") (pintype "output"))
    )
    (net (code "42") (name "Net-(U1-DM)") (class "Default")
      (node (ref "U1") (pin "6") (pinfunction "DM_6") (pintype "bidirectional"))
      (node (ref "U3") (pin "2") (pinfunction "IO2_2") (pintype "bidirectional"))
      (node (ref "USB") (pin "D-") (pinfunction "D-_D-") (pintype "bidirectional"))
    )
    (net (code "43") (name "Net-(U1-DP)") (class "Default")
      (node (ref "U1") (pin "7") (pinfunction "DP_7") (pintype "bidirectional"))
      (node (ref "U3") (pin "1") (pinfunction "IO1_1") (pintype "bidirectional"))
      (node (ref "USB") (pin "D+") (pinfunction "D+_D+") (pintype "bidirectional"))
    )
    (net (code "44") (name "Net-(U1-EECLK)") (class "Default")
      (node (ref "R4") (pin "1") (pinfunction "1_1") (pintype "passive"))
      (node (ref "U1") (pin "44") (pinfunction "EECLK_44") (pintype "output"))
      (node (ref "U2") (pin "4") (pinfunction "CLK_4") (pintype "input"))
    )
    (net (code "45") (name "Net-(U1-EECS)") (class "Default")
      (node (ref "R3") (pin "1") (pinfunction "1_1") (pintype "passive"))
      (node (ref "U1") (pin "45") (pinfunction "EECS_45") (pintype "output"))
      (node (ref "U2") (pin "5") (pinfunction "CS_5") (pintype "input"))
    )
    (net (code "46") (name "Net-(U1-EEDATA)") (class "Default")
      (node (ref "R6") (pin "2") (pinfunction "2_2") (pintype "passive"))
      (node (ref "U1") (pin "43") (pinfunction "EEDATA_43") (pintype "bidirectional"))
      (node (ref "U2") (pin "3") (pinfunction "DI_3") (pintype "input"))
    )
    (net (code "47") (name "Net-(U1-OSCI)") (class "Default")
      (node (ref "C1") (pin "1") (pinfunction "1_1") (pintype "passive"))
      (node (ref "Q1") (pin "1") (pinfunction "1_1") (pintype "passive"))
      (node (ref "U1") (pin "1") (pinfunction "OSCI_1") (pintype "input"))
    )
    (net (code "48") (name "Net-(U1-REF)") (class "Default")
      (node (ref "R1") (pin "2") (pinfunction "2_2") (pintype "passive"))
      (node (ref "U1") (pin "5") (pinfunction "REF_5") (pintype "input"))
    )
    (net (code "49") (name "Net-(U1-RESET#)") (class "Default")
      (node (ref "C3") (pin "1") (pinfunction "1_1") (pintype "passive"))
      (node (ref "R2") (pin "1") (pinfunction "1_1") (pintype "passive"))
      (node (ref "U1") (pin "34") (pinfunction "RESET#_34") (pintype "input"))
    )
    (net (code "50") (name "Net-(U2-DO)") (class "Default")
      (node (ref "R5") (pin "1") (pinfunction "1_1") (pintype "passive"))
      (node (ref "R6") (pin "1") (pinfunction "1_1") (pintype "passive"))
      (node (ref "U2") (pin "1") (pinfunction "DO_1") (pintype "output"))
    )
    (net (code "51") (name "Net-(U3-IO3)") (class "Default")
      (node (ref "U3") (pin "4") (pinfunction "IO3_4") (pintype "bidirectional"))
      (node (ref "USB") (pin "ID") (pinfunction "USBID_ID") (pintype "bidirectional"))
    )
    (net (code "52") (name "Net-(X1-A)") (class "Default")
      (node (ref "X1") (pin "2") (pinfunction "A_2") (pintype "bidirectional"))
      (node (ref "ZED1") (pin "29") (pinfunction "_P_29") (pintype "bidirectional"))
    )
    (net (code "53") (name "Net-(X1-B)") (class "Default")
      (node (ref "X1") (pin "6") (pinfunction "B_6") (pintype "bidirectional"))
      (node (ref "ZED1") (pin "23") (pinfunction "_P_23") (pintype "bidirectional"))
    )
    (net (code "54") (name "Net-(X1-~{A})") (class "Default")
      (node (ref "X1") (pin "3") (pinfunction "~{A}_3") (pintype "bidirectional"))
      (node (ref "ZED1") (pin "31") (pinfunction "_N_31") (pintype "bidirectional"))
    )
    (net (code "55") (name "Net-(X1-~{B})") (class "Default")
      (node (ref "X1") (pin "5") (pinfunction "~{B}_5") (pintype "bidirectional"))
      (node (ref "ZED1") (pin "25") (pinfunction "_N_25") (pintype "bidirectional"))
    )
    (net (code "56") (name "Net-(X2-A)") (class "Default")
      (node (ref "X2") (pin "2") (pinfunction "A_2") (pintype "bidirectional"))
      (node (ref "ZED1") (pin "30") (pinfunction "_P_30") (pintype "bidirectional"))
    )
    (net (code "57") (name "Net-(X2-B)") (class "Default")
      (node (ref "X2") (pin "6") (pinfunction "B_6") (pintype "bidirectional"))
      (node (ref "ZED1") (pin "36") (pinfunction "_P_36") (pintype "bidirectional"))
    )
    (net (code "58") (name "Net-(X2-~{A})") (class "Default")
      (node (ref "X2") (pin "3") (pinfunction "~{A}_3") (pintype "bidirectional"))
      (node (ref "ZED1") (pin "32") (pinfunction "_N_32") (pintype "bidirectional"))
    )
    (net (code "59") (name "Net-(X2-~{B})") (class "Default")
      (node (ref "X2") (pin "5") (pinfunction "~{B}_5") (pintype "bidirectional"))
      (node (ref "ZED1") (pin "38") (pinfunction "_N_38") (pintype "bidirectional"))
    )
    (net (code "60") (name "Net-(X3-A)") (class "Default")
      (node (ref "X3") (pin "2") (pinfunction "A_2") (pintype "bidirectional"))
      (node (ref "ZED1") (pin "135") (pinfunction "_P_135") (pintype "bidirectional"))
    )
    (net (code "61") (name "Net-(X3-B)") (class "Default")
      (node (ref "X3") (pin "6") (pinfunction "B_6") (pintype "bidirectional"))
      (node (ref "ZED1") (pin "129") (pinfunction "_P_129") (pintype "bidirectional"))
    )
    (net (code "62") (name "Net-(X3-~{A})") (class "Default")
      (node (ref "X3") (pin "3") (pinfunction "~{A}_3") (pintype "bidirectional"))
      (node (ref "ZED1") (pin "137") (pinfunction "_N_137") (pintype "bidirectional"))
    )
    (net (code "63") (name "Net-(X3-~{B})") (class "Default")
      (node (ref "X3") (pin "5") (pinfunction "~{B}_5") (pintype "bidirectional"))
      (node (ref "ZED1") (pin "131") (pinfunction "_N_131") (pintype "bidirectional"))
    )
    (net (code "64") (name "Net-(X4-A)") (class "Default")
      (node (ref "X4") (pin "2") (pinfunction "A_2") (pintype "bidirectional"))
      (node (ref "ZED1") (pin "130") (pinfunction "_P_130") (pintype "bidirectional"))
    )
    (net (code "65") (name "Net-(X4-B)") (class "Default")
      (node (ref "X4") (pin "6") (pinfunction "B_6") (pintype "bidirectional"))
      (node (ref "ZED1") (pin "136") (pinfunction "_P_136") (pintype "bidirectional"))
    )
    (net (code "66") (name "Net-(X4-~{A})") (class "Default")
      (node (ref "X4") (pin "3") (pinfunction "~{A}_3") (pintype "bidirectional"))
      (node (ref "ZED1") (pin "132") (pinfunction "_N_132") (pintype "bidirectional"))
    )
    (net (code "67") (name "Net-(X4-~{B})") (class "Default")
      (node (ref "X4") (pin "5") (pinfunction "~{B}_5") (pintype "bidirectional"))
      (node (ref "ZED1") (pin "138") (pinfunction "_N_138") (pintype "bidirectional"))
    )
    (net (code "68") (name "Net-(X5-A)") (class "Default")
      (node (ref "X5") (pin "2") (pinfunction "A_2") (pintype "bidirectional"))
      (node (ref "ZED1") (pin "41") (pinfunction "_P_41") (pintype "bidirectional"))
    )
    (net (code "69") (name "Net-(X5-B)") (class "Default")
      (node (ref "X5") (pin "6") (pinfunction "B_6") (pintype "bidirectional"))
      (node (ref "ZED1") (pin "47") (pinfunction "_P_47") (pintype "bidirectional"))
    )
    (net (code "70") (name "Net-(X5-~{A})") (class "Default")
      (node (ref "X5") (pin "3") (pinfunction "~{A}_3") (pintype "bidirectional"))
      (node (ref "ZED1") (pin "43") (pinfunction "_N_43") (pintype "bidirectional"))
    )
    (net (code "71") (name "Net-(X5-~{B})") (class "Default")
      (node (ref "X5") (pin "5") (pinfunction "~{B}_5") (pintype "bidirectional"))
      (node (ref "ZED1") (pin "49") (pinfunction "_N_49") (pintype "bidirectional"))
    )
    (net (code "72") (name "Net-(X6-A)") (class "Default")
      (node (ref "X6") (pin "2") (pinfunction "A_2") (pintype "bidirectional"))
      (node (ref "ZED1") (pin "42") (pinfunction "_P_42") (pintype "bidirectional"))
    )
    (net (code "73") (name "Net-(X6-B)") (class "Default")
      (node (ref "X6") (pin "6") (pinfunction "B_6") (pintype "bidirectional"))
      (node (ref "ZED1") (pin "48") (pinfunction "_P_48") (pintype "bidirectional"))
    )
    (net (code "74") (name "Net-(X6-~{A})") (class "Default")
      (node (ref "X6") (pin "3") (pinfunction "~{A}_3") (pintype "bidirectional"))
      (node (ref "ZED1") (pin "44") (pinfunction "_N_44") (pintype "bidirectional"))
    )
    (net (code "75") (name "Net-(X6-~{B})") (class "Default")
      (node (ref "X6") (pin "5") (pinfunction "~{B}_5") (pintype "bidirectional"))
      (node (ref "ZED1") (pin "50") (pinfunction "_N_50") (pintype "bidirectional"))
    )
    (net (code "76") (name "Net-(X7-A)") (class "Default")
      (node (ref "X7") (pin "2") (pinfunction "A_2") (pintype "bidirectional"))
      (node (ref "ZED1") (pin "153") (pinfunction "_P_153") (pintype "bidirectional"))
    )
    (net (code "77") (name "Net-(X7-B)") (class "Default")
      (node (ref "X7") (pin "6") (pinfunction "B_6") (pintype "bidirectional"))
      (node (ref "ZED1") (pin "147") (pinfunction "_P_147") (pintype "bidirectional"))
    )
    (net (code "78") (name "Net-(X7-~{A})") (class "Default")
      (node (ref "X7") (pin "3") (pinfunction "~{A}_3") (pintype "bidirectional"))
      (node (ref "ZED1") (pin "155") (pinfunction "_N_155") (pintype "bidirectional"))
    )
    (net (code "79") (name "Net-(X7-~{B})") (class "Default")
      (node (ref "X7") (pin "5") (pinfunction "~{B}_5") (pintype "bidirectional"))
      (node (ref "ZED1") (pin "149") (pinfunction "_N_149") (pintype "bidirectional"))
    )
    (net (code "80") (name "Net-(X8-A)") (class "Default")
      (node (ref "X8") (pin "2") (pinfunction "A_2") (pintype "bidirectional"))
      (node (ref "ZED1") (pin "154") (pinfunction "_P_154") (pintype "bidirectional"))
    )
    (net (code "81") (name "Net-(X8-B)") (class "Default")
      (node (ref "X8") (pin "6") (pinfunction "B_6") (pintype "bidirectional"))
      (node (ref "ZED1") (pin "148") (pinfunction "_P_148") (pintype "bidirectional"))
    )
    (net (code "82") (name "Net-(X8-~{A})") (class "Default")
      (node (ref "X8") (pin "3") (pinfunction "~{A}_3") (pintype "bidirectional"))
      (node (ref "ZED1") (pin "156") (pinfunction "_N_156") (pintype "bidirectional"))
    )
    (net (code "83") (name "Net-(X8-~{B})") (class "Default")
      (node (ref "X8") (pin "5") (pinfunction "~{B}_5") (pintype "bidirectional"))
      (node (ref "ZED1") (pin "150") (pinfunction "_N_150") (pintype "bidirectional"))
    )
    (net (code "84") (name "Net-(X9-A)") (class "Default")
      (node (ref "X9") (pin "2") (pinfunction "A_2") (pintype "bidirectional"))
      (node (ref "ZED1") (pin "168") (pinfunction "_P_168") (pintype "bidirectional"))
    )
    (net (code "85") (name "Net-(X9-B)") (class "Default")
      (node (ref "X9") (pin "6") (pinfunction "B_6") (pintype "bidirectional"))
      (node (ref "ZED1") (pin "174") (pinfunction "_P_174") (pintype "bidirectional"))
    )
    (net (code "86") (name "Net-(X9-~{A})") (class "Default")
      (node (ref "X9") (pin "3") (pinfunction "~{A}_3") (pintype "bidirectional"))
      (node (ref "ZED1") (pin "170") (pinfunction "_N_170") (pintype "bidirectional"))
    )
    (net (code "87") (name "Net-(X9-~{B})") (class "Default")
      (node (ref "X9") (pin "5") (pinfunction "~{B}_5") (pintype "bidirectional"))
      (node (ref "ZED1") (pin "176") (pinfunction "_N_176") (pintype "bidirectional"))
    )
    (net (code "88") (name "Net-(X10-A)") (class "Default")
      (node (ref "X10") (pin "2") (pinfunction "A_2") (pintype "bidirectional"))
      (node (ref "ZED1") (pin "173") (pinfunction "_P_173") (pintype "bidirectional"))
    )
    (net (code "89") (name "Net-(X10-B)") (class "Default")
      (node (ref "X10") (pin "6") (pinfunction "B_6") (pintype "bidirectional"))
      (node (ref "ZED1") (pin "167") (pinfunction "_P_167") (pintype "bidirectional"))
    )
    (net (code "90") (name "Net-(X10-~{A})") (class "Default")
      (node (ref "X10") (pin "3") (pinfunction "~{A}_3") (pintype "bidirectional"))
      (node (ref "ZED1") (pin "175") (pinfunction "_N_175") (pintype "bidirectional"))
    )
    (net (code "91") (name "Net-(X10-~{B})") (class "Default")
      (node (ref "X10") (pin "5") (pinfunction "~{B}_5") (pintype "bidirectional"))
      (node (ref "ZED1") (pin "169") (pinfunction "_N_169") (pintype "bidirectional"))
    )
    (net (code "92") (name "Net-(X11-A)") (class "Default")
      (node (ref "X11") (pin "2") (pinfunction "A_2") (pintype "bidirectional"))
      (node (ref "ZED1") (pin "67") (pinfunction "_P_67") (pintype "bidirectional"))
    )
    (net (code "93") (name "Net-(X11-B)") (class "Default")
      (node (ref "X11") (pin "6") (pinfunction "B_6") (pintype "bidirectional"))
      (node (ref "ZED1") (pin "61") (pinfunction "_P_61") (pintype "bidirectional"))
    )
    (net (code "94") (name "Net-(X11-~{A})") (class "Default")
      (node (ref "X11") (pin "3") (pinfunction "~{A}_3") (pintype "bidirectional"))
      (node (ref "ZED1") (pin "69") (pinfunction "_N_69") (pintype "bidirectional"))
    )
    (net (code "95") (name "Net-(X11-~{B})") (class "Default")
      (node (ref "X11") (pin "5") (pinfunction "~{B}_5") (pintype "bidirectional"))
      (node (ref "ZED1") (pin "63") (pinfunction "_N_63") (pintype "bidirectional"))
    )
    (net (code "96") (name "Net-(X12-A)") (class "Default")
      (node (ref "X12") (pin "2") (pinfunction "A_2") (pintype "bidirectional"))
      (node (ref "ZED1") (pin "62") (pinfunction "_P_62") (pintype "bidirectional"))
    )
    (net (code "97") (name "Net-(X12-B)") (class "Default")
      (node (ref "X12") (pin "6") (pinfunction "B_6") (pintype "bidirectional"))
      (node (ref "ZED1") (pin "68") (pinfunction "_P_68") (pintype "bidirectional"))
    )
    (net (code "98") (name "Net-(X12-~{A})") (class "Default")
      (node (ref "X12") (pin "3") (pinfunction "~{A}_3") (pintype "bidirectional"))
      (node (ref "ZED1") (pin "64") (pinfunction "_N_64") (pintype "bidirectional"))
    )
    (net (code "99") (name "Net-(X12-~{B})") (class "Default")
      (node (ref "X12") (pin "5") (pinfunction "~{B}_5") (pintype "bidirectional"))
      (node (ref "ZED1") (pin "70") (pinfunction "_N_70") (pintype "bidirectional"))
    )
    (net (code "100") (name "Net-(ZED1AG-_N)") (class "Default")
      (node (ref "Y4") (pin "1") (pinfunction "1_1") (pintype "passive"))
      (node (ref "ZED1") (pin "84") (pinfunction "_N_84") (pintype "bidirectional"))
    )
    (net (code "101") (name "Net-(ZED1AG-_P)") (class "Default")
      (node (ref "Y3") (pin "1") (pinfunction "1_1") (pintype "passive"))
      (node (ref "ZED1") (pin "82") (pinfunction "_P_82") (pintype "bidirectional"))
    )
    (net (code "102") (name "Net-(ZED1AK-_N)") (class "Default")
      (node (ref "Y6") (pin "1") (pinfunction "1_1") (pintype "passive"))
      (node (ref "ZED1") (pin "125") (pinfunction "_N_125") (pintype "bidirectional"))
    )
    (net (code "103") (name "Net-(ZED1AK-_P)") (class "Default")
      (node (ref "Y5") (pin "1") (pinfunction "1_1") (pintype "passive"))
      (node (ref "ZED1") (pin "123") (pinfunction "_P_123") (pintype "bidirectional"))
    )
    (net (code "104") (name "Net-(ZED1AR-_N)") (class "Default")
      (node (ref "Z6") (pin "1") (pinfunction "1_1") (pintype "passive"))
      (node (ref "ZED1") (pin "144") (pinfunction "_N_144") (pintype "bidirectional"))
    )
    (net (code "105") (name "Net-(ZED1AR-_P)") (class "Default")
      (node (ref "Z5") (pin "1") (pinfunction "1_1") (pintype "passive"))
      (node (ref "ZED1") (pin "142") (pinfunction "_P_142") (pintype "bidirectional"))
    )
    (net (code "106") (name "Net-(ZED1AX-_N)") (class "Default")
      (node (ref "Z1") (pin "1") (pinfunction "1_1") (pintype "passive"))
      (node (ref "ZED1") (pin "164") (pinfunction "_N_164") (pintype "bidirectional"))
    )
    (net (code "107") (name "Net-(ZED1AX-_P)") (class "Default")
      (node (ref "Z2") (pin "1") (pinfunction "1_1") (pintype "passive"))
      (node (ref "ZED1") (pin "162") (pinfunction "_P_162") (pintype "bidirectional"))
    )
    (net (code "108") (name "Net-(ZED1BC-_N)") (class "Default")
      (node (ref "Y1") (pin "1") (pinfunction "1_1") (pintype "passive"))
      (node (ref "ZED1") (pin "183") (pinfunction "_N_183") (pintype "bidirectional"))
    )
    (net (code "109") (name "Net-(ZED1BC-_P)") (class "Default")
      (node (ref "Y2") (pin "1") (pinfunction "1_1") (pintype "passive"))
      (node (ref "ZED1") (pin "181") (pinfunction "_P_181") (pintype "bidirectional"))
    )
    (net (code "110") (name "Net-(ZED1X-_N)") (class "Default")
      (node (ref "Z4") (pin "1") (pinfunction "1_1") (pintype "passive"))
      (node (ref "ZED1") (pin "55") (pinfunction "_N_55") (pintype "bidirectional"))
    )
    (net (code "111") (name "Net-(ZED1X-_P)") (class "Default")
      (node (ref "Z3") (pin "1") (pinfunction "1_1") (pintype "passive"))
      (node (ref "ZED1") (pin "53") (pinfunction "_P_53") (pintype "bidirectional"))
    )
    (net (code "112") (name "PMOD_A_VCC") (class "Default")
      (node (ref "JP1") (pin "1") (pinfunction "1_1") (pintype "passive"))
      (node (ref "PAD12") (pin "1") (pinfunction "P_1") (pintype "passive"))
      (node (ref "PAD6") (pin "1") (pinfunction "P_1") (pintype "passive"))
    )
    (net (code "113") (name "PMOD_B_VCC") (class "Default")
      (node (ref "JP2") (pin "1") (pinfunction "1_1") (pintype "passive"))
      (node (ref "PAD18") (pin "1") (pinfunction "P_1") (pintype "passive"))
      (node (ref "PAD24") (pin "1") (pinfunction "P_1") (pintype "passive"))
    )
    (net (code "114") (name "PMOD_C_VCC") (class "Default")
      (node (ref "JP3") (pin "2") (pinfunction "2_2") (pintype "passive"))
      (node (ref "PAD30") (pin "1") (pinfunction "P_1") (pintype "passive"))
      (node (ref "PAD36") (pin "1") (pinfunction "P_1") (pintype "passive"))
    )
    (net (code "115") (name "PMOD_D_VCC") (class "Default")
      (node (ref "JP4") (pin "2") (pinfunction "2_2") (pintype "passive"))
      (node (ref "PAD42") (pin "1") (pinfunction "P_1") (pintype "passive"))
      (node (ref "PAD48") (pin "1") (pinfunction "P_1") (pintype "passive"))
    )
    (net (code "116") (name "VCCA") (class "Default")
      (node (ref "C6") (pin "1") (pinfunction "1_1") (pintype "passive"))
      (node (ref "U1") (pin "37") (pinfunction "VCCA_37") (pintype "output"))
    )
    (net (code "117") (name "VCCD") (class "Default")
      (node (ref "FB2") (pin "1") (pinfunction "P$1_1") (pintype "passive"))
      (node (ref "FB3") (pin "1") (pinfunction "P$1_1") (pintype "passive"))
      (node (ref "R2") (pin "2") (pinfunction "2_2") (pintype "passive"))
      (node (ref "R3") (pin "2") (pinfunction "2_2") (pintype "passive"))
      (node (ref "R4") (pin "2") (pinfunction "2_2") (pintype "passive"))
      (node (ref "R5") (pin "2") (pinfunction "2_2") (pintype "passive"))
      (node (ref "U1") (pin "12") (pinfunction "VCCIO_12") (pintype "power_in"))
      (node (ref "U1") (pin "24") (pinfunction "VCCIO_24") (pintype "power_in"))
      (node (ref "U1") (pin "39") (pinfunction "VCCD_39") (pintype "power_in"))
      (node (ref "U1") (pin "46") (pinfunction "VCCIO_46") (pintype "power_in"))
      (node (ref "U2") (pin "6") (pinfunction "VCC_6") (pintype "power_in"))
    )
    (net (code "118") (name "VCCO_13") (class "Default")
      (node (ref "JP2") (pin "2") (pinfunction "2_2") (pintype "passive"))
      (node (ref "ZED1") (pin "198") (pinfunction "VCCO_13_198") (pintype "power_in"))
    )
    (net (code "119") (name "VCCO_34") (class "Default")
      (node (ref "JP3") (pin "1") (pinfunction "1_1") (pintype "passive"))
      (node (ref "ZED1") (pin "78") (pinfunction "VCCO_34_78") (pintype "power_in"))
      (node (ref "ZED1") (pin "79") (pinfunction "VCCO_34_79") (pintype "power_in"))
      (node (ref "ZED1") (pin "80") (pinfunction "VCCO_34_80") (pintype "power_in"))
    )
    (net (code "120") (name "VCCO_35") (class "Default")
      (node (ref "JP2") (pin "3") (pinfunction "3_3") (pintype "passive"))
      (node (ref "ZED1") (pin "178") (pinfunction "VCCO_35_178") (pintype "power_in"))
      (node (ref "ZED1") (pin "179") (pinfunction "VCCO_35_179") (pintype "power_in"))
      (node (ref "ZED1") (pin "180") (pinfunction "VCCO_35_180") (pintype "power_in"))
    )
    (net (code "121") (name "VCORE") (class "Default")
      (node (ref "C5") (pin "1") (pinfunction "1_1") (pintype "passive"))
      (node (ref "U1") (pin "38") (pinfunction "VCORE_38") (pintype "output"))
    )
    (net (code "122") (name "VIN_HDR") (class "Default")
      (node (ref "JP1") (pin "2") (pinfunction "2_2") (pintype "passive"))
      (node (ref "JP4") (pin "1") (pinfunction "1_1") (pintype "passive"))
      (node (ref "ZED1") (pin "112") (pinfunction "VIN_HDR_112") (pintype "power_in"))
      (node (ref "ZED1") (pin "157") (pinfunction "VIN_HDR_157") (pintype "power_in"))
      (node (ref "ZED1") (pin "158") (pinfunction "VIN_HDR_158") (pintype "power_in"))
      (node (ref "ZED1") (pin "159") (pinfunction "VIN_HDR_159") (pintype "power_in"))
      (node (ref "ZED1") (pin "160") (pinfunction "VIN_HDR_160") (pintype "power_in"))
      (node (ref "ZED1") (pin "57") (pinfunction "VIN_HDR_57") (pintype "power_in"))
      (node (ref "ZED1") (pin "58") (pinfunction "VIN_HDR_58") (pintype "power_in"))
      (node (ref "ZED1") (pin "59") (pinfunction "VIN_HDR_59") (pintype "power_in"))
      (node (ref "ZED1") (pin "60") (pinfunction "VIN_HDR_60") (pintype "power_in"))
    )
    (net (code "123") (name "VPHY") (class "Default")
      (node (ref "C7") (pin "1") (pinfunction "1_1") (pintype "passive"))
      (node (ref "C8") (pin "1") (pinfunction "1_1") (pintype "passive"))
      (node (ref "FB2") (pin "2") (pinfunction "P$2_2") (pintype "passive"))
      (node (ref "U1") (pin "3") (pinfunction "VPHY_3") (pintype "power_in"))
    )
    (net (code "124") (name "VPLL") (class "Default")
      (node (ref "C10") (pin "1") (pinfunction "1_1") (pintype "passive"))
      (node (ref "C9") (pin "1") (pinfunction "1_1") (pintype "passive"))
      (node (ref "FB3") (pin "2") (pinfunction "P$2_2") (pintype "passive"))
      (node (ref "U1") (pin "8") (pinfunction "VPLL_8") (pintype "power_in"))
    )
    (net (code "125") (name "unconnected-(U1-ACBUS0-Pad21)") (class "Default")
      (node (ref "U1") (pin "21") (pinfunction "ACBUS0_21") (pintype "bidirectional"))
    )
    (net (code "126") (name "unconnected-(U1-ACBUS1-Pad25)") (class "Default")
      (node (ref "U1") (pin "25") (pinfunction "ACBUS1_25") (pintype "bidirectional"))
    )
    (net (code "127") (name "unconnected-(U1-ACBUS2-Pad26)") (class "Default")
      (node (ref "U1") (pin "26") (pinfunction "ACBUS2_26") (pintype "bidirectional"))
    )
    (net (code "128") (name "unconnected-(U1-ACBUS3-Pad27)") (class "Default")
      (node (ref "U1") (pin "27") (pinfunction "ACBUS3_27") (pintype "bidirectional"))
    )
    (net (code "129") (name "unconnected-(U1-ACBUS4-Pad28)") (class "Default")
      (node (ref "U1") (pin "28") (pinfunction "ACBUS4_28") (pintype "bidirectional"))
    )
    (net (code "130") (name "unconnected-(U1-ACBUS5-Pad29)") (class "Default")
      (node (ref "U1") (pin "29") (pinfunction "ACBUS5_29") (pintype "bidirectional"))
    )
    (net (code "131") (name "unconnected-(U1-ACBUS6-Pad30)") (class "Default")
      (node (ref "U1") (pin "30") (pinfunction "ACBUS6_30") (pintype "bidirectional"))
    )
    (net (code "132") (name "unconnected-(U1-ACBUS7-Pad31)") (class "Default")
      (node (ref "U1") (pin "31") (pinfunction "ACBUS7_31") (pintype "bidirectional"))
    )
    (net (code "133") (name "unconnected-(U1-ACBUS8-Pad32)") (class "Default")
      (node (ref "U1") (pin "32") (pinfunction "ACBUS8_32") (pintype "bidirectional"))
    )
    (net (code "134") (name "unconnected-(U1-ACBUS9-Pad33)") (class "Default")
      (node (ref "U1") (pin "33") (pinfunction "ACBUS9_33") (pintype "bidirectional"))
    )
    (net (code "135") (name "unconnected-(U1-ADBUS4-Pad17)") (class "Default")
      (node (ref "U1") (pin "17") (pinfunction "ADBUS4_17") (pintype "output"))
    )
    (net (code "136") (name "unconnected-(U1-ADBUS5-Pad18)") (class "Default")
      (node (ref "U1") (pin "18") (pinfunction "ADBUS5_18") (pintype "input"))
    )
    (net (code "137") (name "unconnected-(U1-ADBUS6-Pad19)") (class "Default")
      (node (ref "U1") (pin "19") (pinfunction "ADBUS6_19") (pintype "input"))
    )
    (net (code "138") (name "unconnected-(U1-ADBUS7-Pad20)") (class "Default")
      (node (ref "U1") (pin "20") (pinfunction "ADBUS7_20") (pintype "input"))
    )
    (net (code "139") (name "unconnected-(U1-TEST-Pad42)") (class "Default")
      (node (ref "U1") (pin "42") (pinfunction "TEST_42") (pintype "input"))
    )
    (net (code "140") (name "unconnected-(ZED1AD-_N-Pad75)") (class "Default")
      (node (ref "ZED1") (pin "75") (pinfunction "_N_75") (pintype "bidirectional"))
    )
    (net (code "141") (name "unconnected-(ZED1AD-_P-Pad73)") (class "Default")
      (node (ref "ZED1") (pin "73") (pinfunction "_P_73") (pintype "bidirectional"))
    )
    (net (code "142") (name "unconnected-(ZED1AE-_N-Pad76)") (class "Default")
      (node (ref "ZED1") (pin "76") (pinfunction "_N_76") (pintype "bidirectional"))
    )
    (net (code "143") (name "unconnected-(ZED1AE-_P-Pad74)") (class "Default")
      (node (ref "ZED1") (pin "74") (pinfunction "_P_74") (pintype "bidirectional"))
    )
    (net (code "144") (name "unconnected-(ZED1AF-_N-Pad83)") (class "Default")
      (node (ref "ZED1") (pin "83") (pinfunction "_N_83") (pintype "bidirectional"))
    )
    (net (code "145") (name "unconnected-(ZED1AF-_P-Pad81)") (class "Default")
      (node (ref "ZED1") (pin "81") (pinfunction "_P_81") (pintype "bidirectional"))
    )
    (net (code "146") (name "unconnected-(ZED1AH-_0-Pad9)") (class "Default")
      (node (ref "ZED1") (pin "9") (pinfunction "_0_9") (pintype "bidirectional"))
    )
    (net (code "147") (name "unconnected-(ZED1AH-_1-Pad10)") (class "Default")
      (node (ref "ZED1") (pin "10") (pinfunction "_1_10") (pintype "bidirectional"))
    )
    (net (code "148") (name "unconnected-(ZED1AW-_N-Pad163)") (class "Default")
      (node (ref "ZED1") (pin "163") (pinfunction "_N_163") (pintype "bidirectional"))
    )
    (net (code "149") (name "unconnected-(ZED1AW-_P-Pad161)") (class "Default")
      (node (ref "ZED1") (pin "161") (pinfunction "_P_161") (pintype "bidirectional"))
    )
    (net (code "150") (name "unconnected-(ZED1BE-_N-Pad189)") (class "Default")
      (node (ref "ZED1") (pin "189") (pinfunction "_N_189") (pintype "bidirectional"))
    )
    (net (code "151") (name "unconnected-(ZED1BE-_P-Pad187)") (class "Default")
      (node (ref "ZED1") (pin "187") (pinfunction "_P_187") (pintype "bidirectional"))
    )
    (net (code "152") (name "unconnected-(ZED1BG-_0-Pad113)") (class "Default")
      (node (ref "ZED1") (pin "113") (pinfunction "_0_113") (pintype "bidirectional"))
    )
    (net (code "153") (name "unconnected-(ZED1BG-_1-Pad114)") (class "Default")
      (node (ref "ZED1") (pin "114") (pinfunction "_1_114") (pintype "bidirectional"))
    )
    (net (code "154") (name "unconnected-(ZED1BH-_N-Pad99)") (class "Default")
      (node (ref "ZED1") (pin "99") (pinfunction "_N_99") (pintype "bidirectional"))
    )
    (net (code "155") (name "unconnected-(ZED1BH-_P-Pad97)") (class "Default")
      (node (ref "ZED1") (pin "97") (pinfunction "_P_97") (pintype "bidirectional"))
    )
    (net (code "156") (name "unconnected-(ZED1BI-FPGA_DONE-Pad8)") (class "Default")
      (node (ref "ZED1") (pin "8") (pinfunction "FPGA_DONE_8") (pintype "output"))
    )
    (net (code "157") (name "unconnected-(ZED1BI-PG_MODULE-Pad111)") (class "Default")
      (node (ref "ZED1") (pin "111") (pinfunction "PG_MODULE_111") (pintype "output"))
    )
    (net (code "158") (name "unconnected-(ZED1BI-PWR_ENABLE-Pad5)") (class "Default")
      (node (ref "ZED1") (pin "5") (pinfunction "PWR_ENABLE_5") (pintype "input"))
    )
    (net (code "159") (name "unconnected-(ZED1BI-~{CARRIER_SRST}-Pad6)") (class "Default")
      (node (ref "ZED1") (pin "6") (pinfunction "~{CARRIER_SRST}_6") (pintype "output"))
    )
    (net (code "160") (name "unconnected-(ZED1BI-~{INIT}-Pad109)") (class "Default")
      (node (ref "ZED1") (pin "109") (pinfunction "~{INIT}_109") (pintype "input"))
    )
    (net (code "161") (name "unconnected-(ZED1BI-~{PROGRAM}-Pad110)") (class "Default")
      (node (ref "ZED1") (pin "110") (pinfunction "~{PROGRAM}_110") (pintype "input"))
    )
    (net (code "162") (name "unconnected-(ZED1F-_N-Pad196)") (class "Default")
      (node (ref "ZED1") (pin "196") (pinfunction "_N_196") (pintype "bidirectional"))
    )
    (net (code "163") (name "unconnected-(ZED1F-_P-Pad194)") (class "Default")
      (node (ref "ZED1") (pin "194") (pinfunction "_P_194") (pintype "bidirectional"))
    )
    (net (code "164") (name "unconnected-(ZED1H-_0-Pad200)") (class "Default")
      (node (ref "ZED1") (pin "200") (pinfunction "_0_200") (pintype "bidirectional"))
    )
    (net (code "165") (name "unconnected-(ZED1I-_N-Pad100)") (class "Default")
      (node (ref "ZED1") (pin "100") (pinfunction "_N_100") (pintype "bidirectional"))
    )
    (net (code "166") (name "unconnected-(ZED1I-_P-Pad98)") (class "Default")
      (node (ref "ZED1") (pin "98") (pinfunction "_P_98") (pintype "bidirectional"))
    )
    (net (code "167") (name "unconnected-(ZED1O-_N-Pad26)") (class "Default")
      (node (ref "ZED1") (pin "26") (pinfunction "_N_26") (pintype "bidirectional"))
    )
    (net (code "168") (name "unconnected-(ZED1O-_P-Pad24)") (class "Default")
      (node (ref "ZED1") (pin "24") (pinfunction "_P_24") (pintype "bidirectional"))
    )
    (net (code "169") (name "unconnected-(ZED1R-_N-Pad37)") (class "Default")
      (node (ref "ZED1") (pin "37") (pinfunction "_N_37") (pintype "bidirectional"))
    )
    (net (code "170") (name "unconnected-(ZED1R-_P-Pad35)") (class "Default")
      (node (ref "ZED1") (pin "35") (pinfunction "_P_35") (pintype "bidirectional"))
    )
    (net (code "171") (name "unconnected-(ZED1Y-_N-Pad56)") (class "Default")
      (node (ref "ZED1") (pin "56") (pinfunction "_N_56") (pintype "bidirectional"))
    )
    (net (code "172") (name "unconnected-(ZED1Y-_P-Pad54)") (class "Default")
      (node (ref "ZED1") (pin "54") (pinfunction "_P_54") (pintype "bidirectional"))
    )
  )
)
